# UCirKit30x20-0721.net
KiCad netlist of a schematic drawn in EAGLE
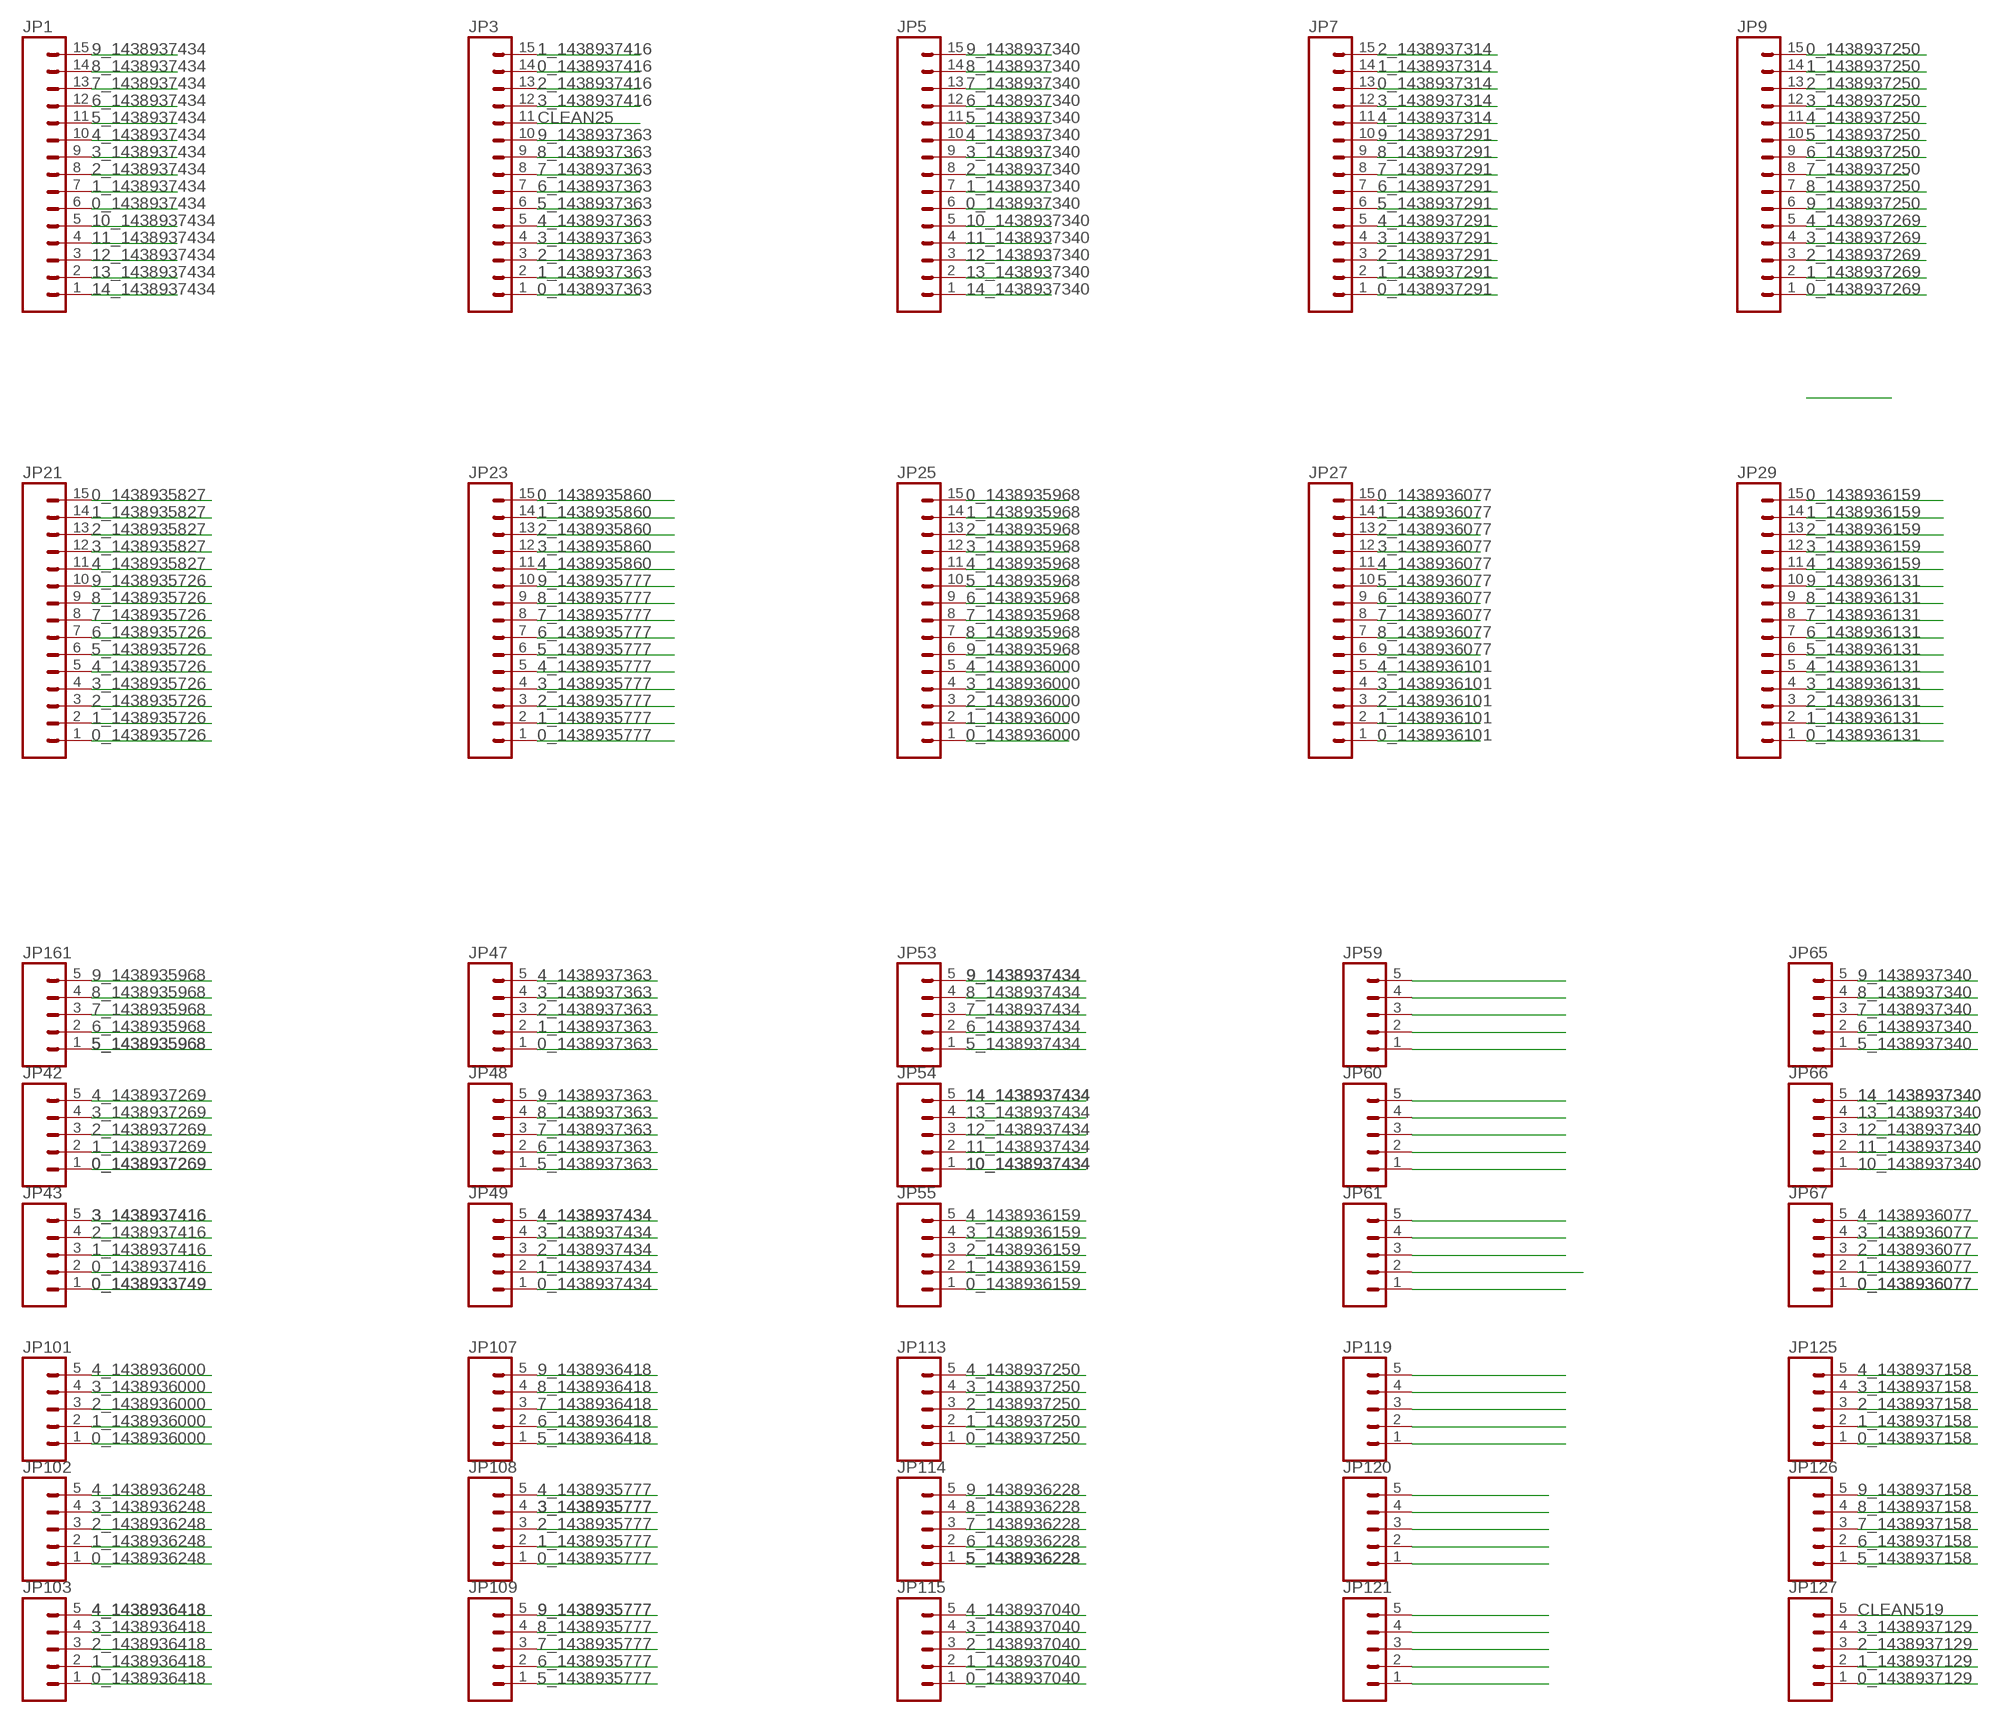
[diagram p0: schematic, sheet 1, part 1 of 2]
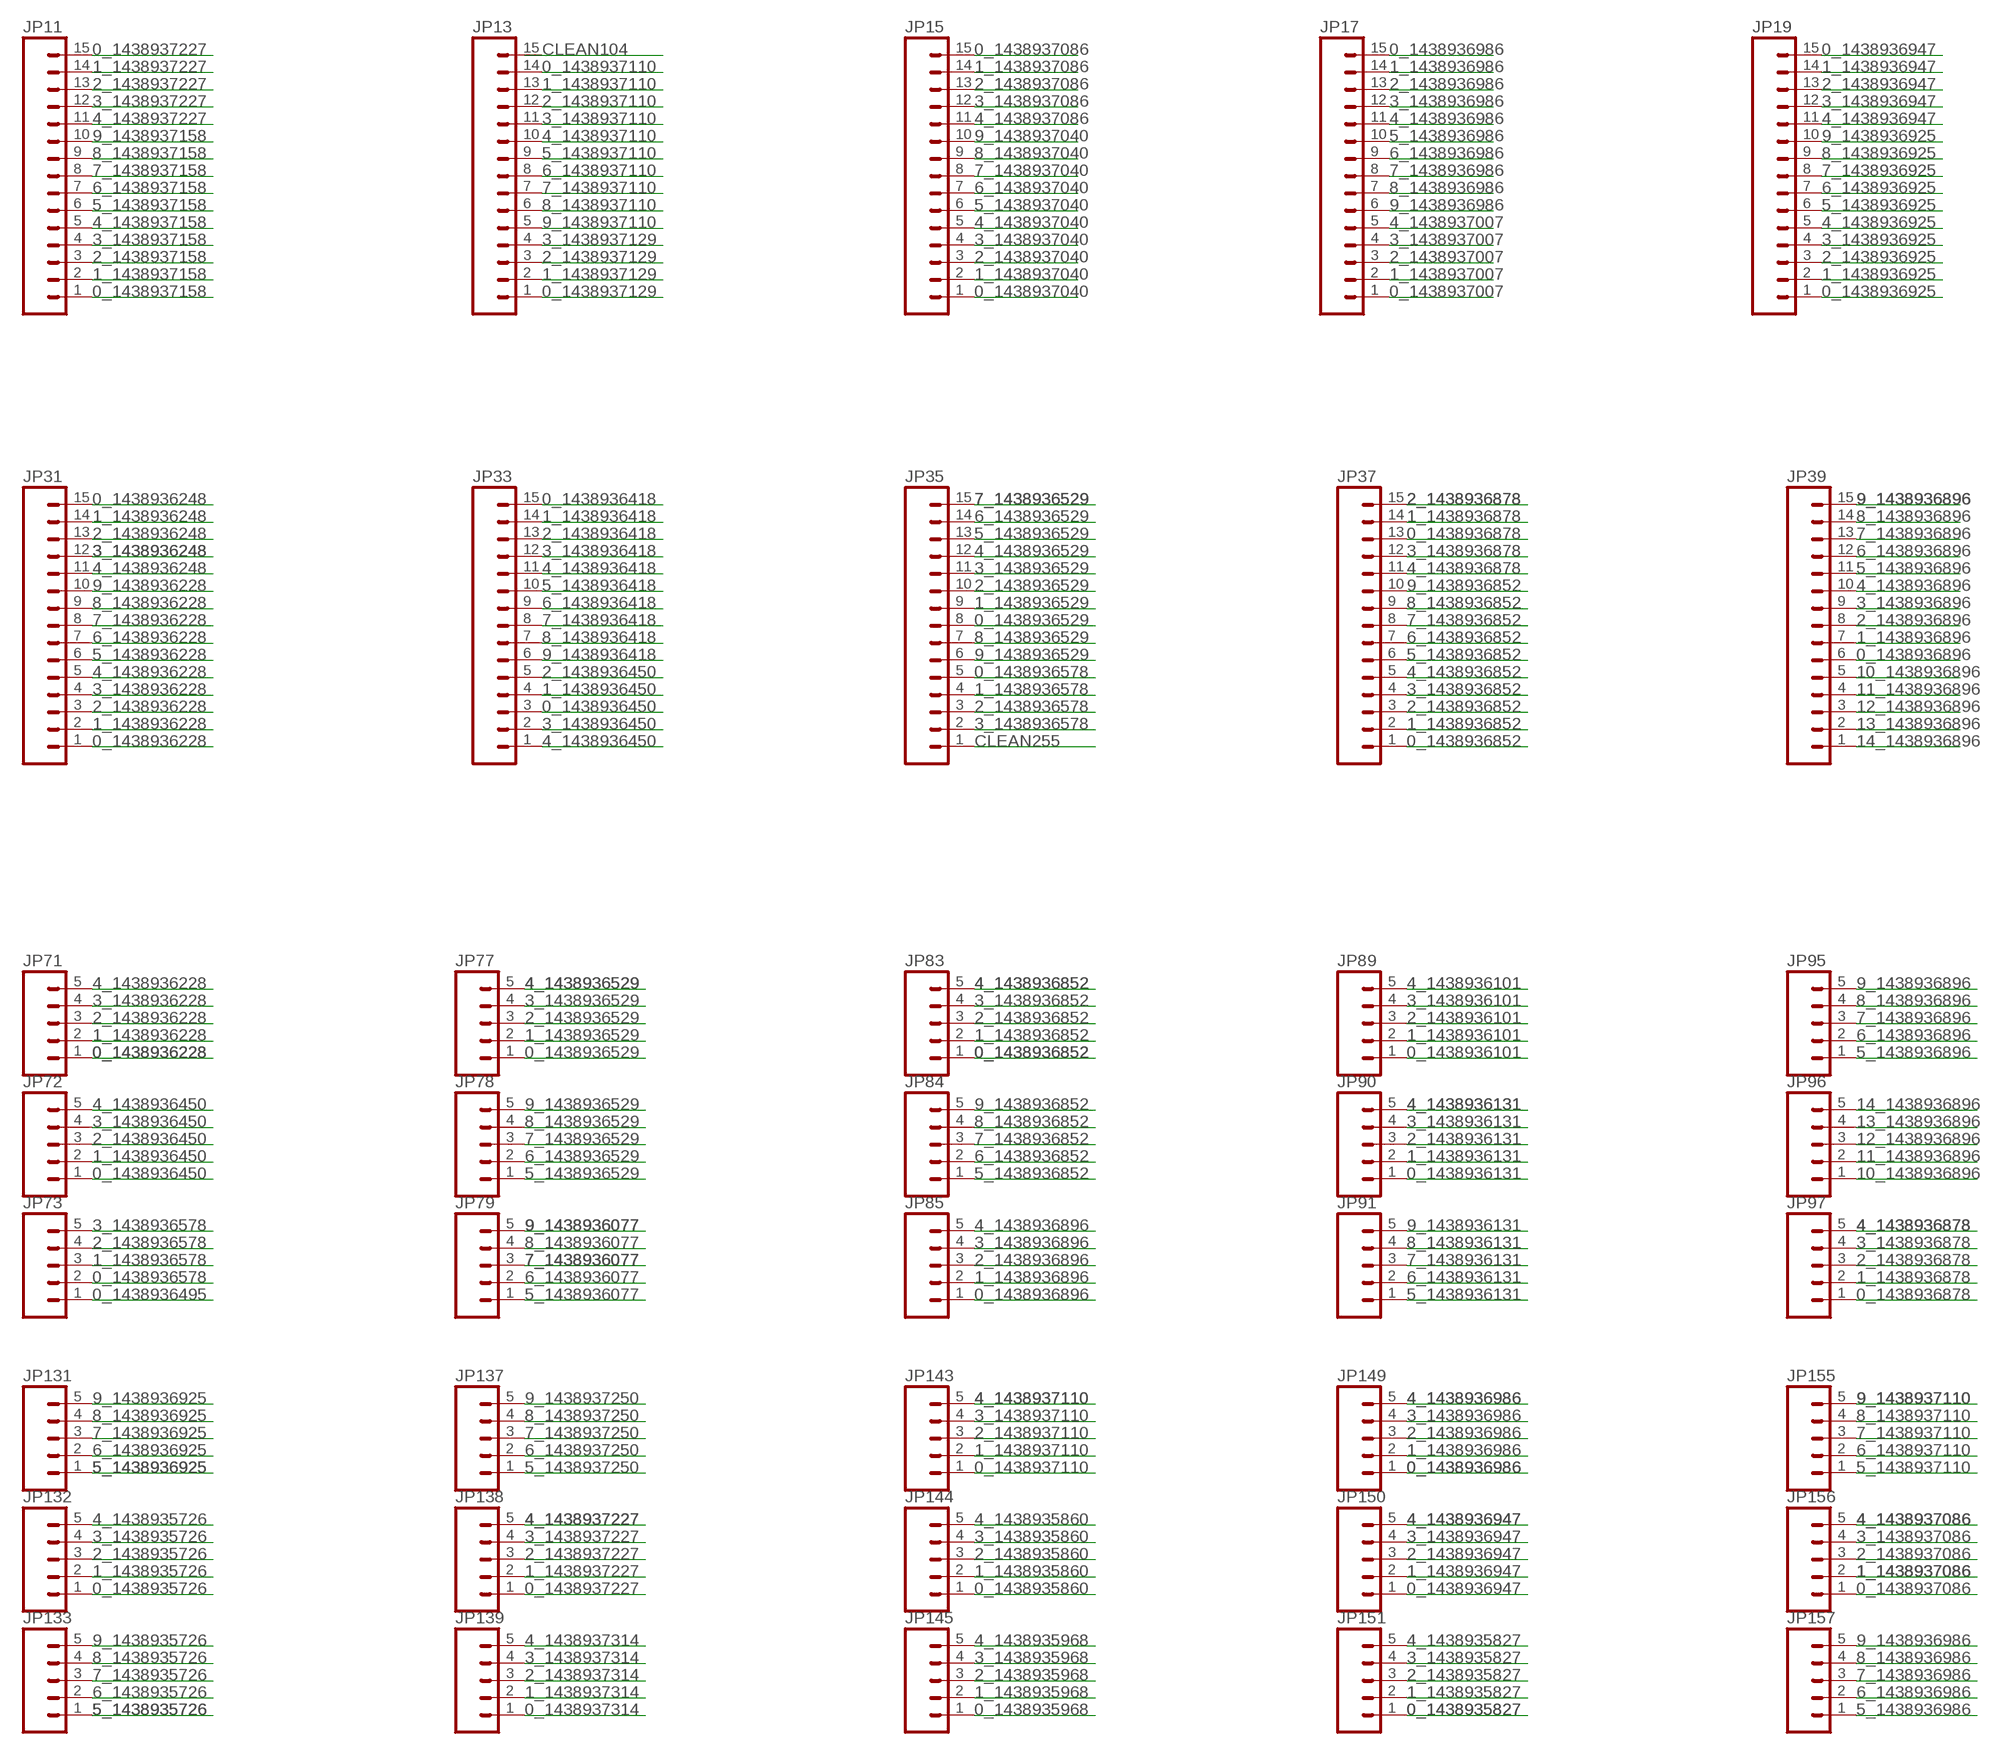
[diagram p1: schematic, sheet 1, part 2 of 2]

(export (version "E")
  (design (tool "Eeschema 10.0.6"))
  (components
    (comp (ref "JP1")
      (value "M15")
      (footprint "eagle-import:1X15")
      (libsource (lib "eagle-import") (part "M15"))
    )
    (comp (ref "JP3")
      (value "M15")
      (footprint "eagle-import:1X15")
      (libsource (lib "eagle-import") (part "M15"))
    )
    (comp (ref "JP5")
      (value "M15")
      (footprint "eagle-import:1X15")
      (libsource (lib "eagle-import") (part "M15"))
    )
    (comp (ref "JP7")
      (value "M15")
      (footprint "eagle-import:1X15")
      (libsource (lib "eagle-import") (part "M15"))
    )
    (comp (ref "JP9")
      (value "M15")
      (footprint "eagle-import:1X15")
      (libsource (lib "eagle-import") (part "M15"))
    )
    (comp (ref "JP11")
      (value "M15")
      (footprint "eagle-import:1X15")
      (libsource (lib "eagle-import") (part "M15"))
    )
    (comp (ref "JP13")
      (value "M15")
      (footprint "eagle-import:1X15")
      (libsource (lib "eagle-import") (part "M15"))
    )
    (comp (ref "JP15")
      (value "M15")
      (footprint "eagle-import:1X15")
      (libsource (lib "eagle-import") (part "M15"))
    )
    (comp (ref "JP17")
      (value "M15")
      (footprint "eagle-import:1X15")
      (libsource (lib "eagle-import") (part "M15"))
    )
    (comp (ref "JP19")
      (value "M15")
      (footprint "eagle-import:1X15")
      (libsource (lib "eagle-import") (part "M15"))
    )
    (comp (ref "JP21")
      (value "M15")
      (footprint "eagle-import:1X15")
      (libsource (lib "eagle-import") (part "M15"))
    )
    (comp (ref "JP23")
      (value "M15")
      (footprint "eagle-import:1X15")
      (libsource (lib "eagle-import") (part "M15"))
    )
    (comp (ref "JP25")
      (value "M15")
      (footprint "eagle-import:1X15")
      (libsource (lib "eagle-import") (part "M15"))
    )
    (comp (ref "JP27")
      (value "M15")
      (footprint "eagle-import:1X15")
      (libsource (lib "eagle-import") (part "M15"))
    )
    (comp (ref "JP29")
      (value "M15")
      (footprint "eagle-import:1X15")
      (libsource (lib "eagle-import") (part "M15"))
    )
    (comp (ref "JP31")
      (value "M15")
      (footprint "eagle-import:1X15")
      (libsource (lib "eagle-import") (part "M15"))
    )
    (comp (ref "JP33")
      (value "M15")
      (footprint "eagle-import:1X15")
      (libsource (lib "eagle-import") (part "M15"))
    )
    (comp (ref "JP35")
      (value "M15")
      (footprint "eagle-import:1X15")
      (libsource (lib "eagle-import") (part "M15"))
    )
    (comp (ref "JP37")
      (value "M15")
      (footprint "eagle-import:1X15")
      (libsource (lib "eagle-import") (part "M15"))
    )
    (comp (ref "JP39")
      (value "M15")
      (footprint "eagle-import:1X15")
      (libsource (lib "eagle-import") (part "M15"))
    )
    (comp (ref "JP42")
      (value "M051.27MM")
      (footprint "eagle-import:1X05-1.27MM")
      (libsource (lib "eagle-import") (part "M051.27MM"))
    )
    (comp (ref "JP43")
      (value "M051.27MM")
      (footprint "eagle-import:1X05-1.27MM")
      (libsource (lib "eagle-import") (part "M051.27MM"))
    )
    (comp (ref "JP47")
      (value "M051.27MM")
      (footprint "eagle-import:1X05-1.27MM")
      (libsource (lib "eagle-import") (part "M051.27MM"))
    )
    (comp (ref "JP48")
      (value "M051.27MM")
      (footprint "eagle-import:1X05-1.27MM")
      (libsource (lib "eagle-import") (part "M051.27MM"))
    )
    (comp (ref "JP49")
      (value "M051.27MM")
      (footprint "eagle-import:1X05-1.27MM")
      (libsource (lib "eagle-import") (part "M051.27MM"))
    )
    (comp (ref "JP53")
      (value "M051.27MM")
      (footprint "eagle-import:1X05-1.27MM")
      (libsource (lib "eagle-import") (part "M051.27MM"))
    )
    (comp (ref "JP54")
      (value "M051.27MM")
      (footprint "eagle-import:1X05-1.27MM")
      (libsource (lib "eagle-import") (part "M051.27MM"))
    )
    (comp (ref "JP55")
      (value "M051.27MM")
      (footprint "eagle-import:1X05-1.27MM")
      (libsource (lib "eagle-import") (part "M051.27MM"))
    )
    (comp (ref "JP59")
      (value "M051.27MM")
      (footprint "eagle-import:1X05-1.27MM")
      (libsource (lib "eagle-import") (part "M051.27MM"))
    )
    (comp (ref "JP60")
      (value "M051.27MM")
      (footprint "eagle-import:1X05-1.27MM")
      (libsource (lib "eagle-import") (part "M051.27MM"))
    )
    (comp (ref "JP61")
      (value "M051.27MM")
      (footprint "eagle-import:1X05-1.27MM")
      (libsource (lib "eagle-import") (part "M051.27MM"))
    )
    (comp (ref "JP65")
      (value "M051.27MM")
      (footprint "eagle-import:1X05-1.27MM")
      (libsource (lib "eagle-import") (part "M051.27MM"))
    )
    (comp (ref "JP66")
      (value "M051.27MM")
      (footprint "eagle-import:1X05-1.27MM")
      (libsource (lib "eagle-import") (part "M051.27MM"))
    )
    (comp (ref "JP67")
      (value "M051.27MM")
      (footprint "eagle-import:1X05-1.27MM")
      (libsource (lib "eagle-import") (part "M051.27MM"))
    )
    (comp (ref "JP71")
      (value "M051.27MM")
      (footprint "eagle-import:1X05-1.27MM")
      (libsource (lib "eagle-import") (part "M051.27MM"))
    )
    (comp (ref "JP72")
      (value "M051.27MM")
      (footprint "eagle-import:1X05-1.27MM")
      (libsource (lib "eagle-import") (part "M051.27MM"))
    )
    (comp (ref "JP73")
      (value "M051.27MM")
      (footprint "eagle-import:1X05-1.27MM")
      (libsource (lib "eagle-import") (part "M051.27MM"))
    )
    (comp (ref "JP77")
      (value "M051.27MM")
      (footprint "eagle-import:1X05-1.27MM")
      (libsource (lib "eagle-import") (part "M051.27MM"))
    )
    (comp (ref "JP78")
      (value "M051.27MM")
      (footprint "eagle-import:1X05-1.27MM")
      (libsource (lib "eagle-import") (part "M051.27MM"))
    )
    (comp (ref "JP79")
      (value "M051.27MM")
      (footprint "eagle-import:1X05-1.27MM")
      (libsource (lib "eagle-import") (part "M051.27MM"))
    )
    (comp (ref "JP83")
      (value "M051.27MM")
      (footprint "eagle-import:1X05-1.27MM")
      (libsource (lib "eagle-import") (part "M051.27MM"))
    )
    (comp (ref "JP84")
      (value "M051.27MM")
      (footprint "eagle-import:1X05-1.27MM")
      (libsource (lib "eagle-import") (part "M051.27MM"))
    )
    (comp (ref "JP85")
      (value "M051.27MM")
      (footprint "eagle-import:1X05-1.27MM")
      (libsource (lib "eagle-import") (part "M051.27MM"))
    )
    (comp (ref "JP89")
      (value "M051.27MM")
      (footprint "eagle-import:1X05-1.27MM")
      (libsource (lib "eagle-import") (part "M051.27MM"))
    )
    (comp (ref "JP90")
      (value "M051.27MM")
      (footprint "eagle-import:1X05-1.27MM")
      (libsource (lib "eagle-import") (part "M051.27MM"))
    )
    (comp (ref "JP91")
      (value "M051.27MM")
      (footprint "eagle-import:1X05-1.27MM")
      (libsource (lib "eagle-import") (part "M051.27MM"))
    )
    (comp (ref "JP95")
      (value "M051.27MM")
      (footprint "eagle-import:1X05-1.27MM")
      (libsource (lib "eagle-import") (part "M051.27MM"))
    )
    (comp (ref "JP96")
      (value "M051.27MM")
      (footprint "eagle-import:1X05-1.27MM")
      (libsource (lib "eagle-import") (part "M051.27MM"))
    )
    (comp (ref "JP97")
      (value "M051.27MM")
      (footprint "eagle-import:1X05-1.27MM")
      (libsource (lib "eagle-import") (part "M051.27MM"))
    )
    (comp (ref "JP101")
      (value "M051.27MM")
      (footprint "eagle-import:1X05-1.27MM")
      (libsource (lib "eagle-import") (part "M051.27MM"))
    )
    (comp (ref "JP102")
      (value "M051.27MM")
      (footprint "eagle-import:1X05-1.27MM")
      (libsource (lib "eagle-import") (part "M051.27MM"))
    )
    (comp (ref "JP103")
      (value "M051.27MM")
      (footprint "eagle-import:1X05-1.27MM")
      (libsource (lib "eagle-import") (part "M051.27MM"))
    )
    (comp (ref "JP107")
      (value "M051.27MM")
      (footprint "eagle-import:1X05-1.27MM")
      (libsource (lib "eagle-import") (part "M051.27MM"))
    )
    (comp (ref "JP108")
      (value "M051.27MM")
      (footprint "eagle-import:1X05-1.27MM")
      (libsource (lib "eagle-import") (part "M051.27MM"))
    )
    (comp (ref "JP109")
      (value "M051.27MM")
      (footprint "eagle-import:1X05-1.27MM")
      (libsource (lib "eagle-import") (part "M051.27MM"))
    )
    (comp (ref "JP113")
      (value "M051.27MM")
      (footprint "eagle-import:1X05-1.27MM")
      (libsource (lib "eagle-import") (part "M051.27MM"))
    )
    (comp (ref "JP114")
      (value "M051.27MM")
      (footprint "eagle-import:1X05-1.27MM")
      (libsource (lib "eagle-import") (part "M051.27MM"))
    )
    (comp (ref "JP115")
      (value "M051.27MM")
      (footprint "eagle-import:1X05-1.27MM")
      (libsource (lib "eagle-import") (part "M051.27MM"))
    )
    (comp (ref "JP119")
      (value "M051.27MM")
      (footprint "eagle-import:1X05-1.27MM")
      (libsource (lib "eagle-import") (part "M051.27MM"))
    )
    (comp (ref "JP120")
      (value "M051.27MM")
      (footprint "eagle-import:1X05-1.27MM")
      (libsource (lib "eagle-import") (part "M051.27MM"))
    )
    (comp (ref "JP121")
      (value "M051.27MM")
      (footprint "eagle-import:1X05-1.27MM")
      (libsource (lib "eagle-import") (part "M051.27MM"))
    )
    (comp (ref "JP125")
      (value "M051.27MM")
      (footprint "eagle-import:1X05-1.27MM")
      (libsource (lib "eagle-import") (part "M051.27MM"))
    )
    (comp (ref "JP126")
      (value "M051.27MM")
      (footprint "eagle-import:1X05-1.27MM")
      (libsource (lib "eagle-import") (part "M051.27MM"))
    )
    (comp (ref "JP127")
      (value "M051.27MM")
      (footprint "eagle-import:1X05-1.27MM")
      (libsource (lib "eagle-import") (part "M051.27MM"))
    )
    (comp (ref "JP131")
      (value "M051.27MM")
      (footprint "eagle-import:1X05-1.27MM")
      (libsource (lib "eagle-import") (part "M051.27MM"))
    )
    (comp (ref "JP132")
      (value "M051.27MM")
      (footprint "eagle-import:1X05-1.27MM")
      (libsource (lib "eagle-import") (part "M051.27MM"))
    )
    (comp (ref "JP133")
      (value "M051.27MM")
      (footprint "eagle-import:1X05-1.27MM")
      (libsource (lib "eagle-import") (part "M051.27MM"))
    )
    (comp (ref "JP137")
      (value "M051.27MM")
      (footprint "eagle-import:1X05-1.27MM")
      (libsource (lib "eagle-import") (part "M051.27MM"))
    )
    (comp (ref "JP138")
      (value "M051.27MM")
      (footprint "eagle-import:1X05-1.27MM")
      (libsource (lib "eagle-import") (part "M051.27MM"))
    )
    (comp (ref "JP139")
      (value "M051.27MM")
      (footprint "eagle-import:1X05-1.27MM")
      (libsource (lib "eagle-import") (part "M051.27MM"))
    )
    (comp (ref "JP143")
      (value "M051.27MM")
      (footprint "eagle-import:1X05-1.27MM")
      (libsource (lib "eagle-import") (part "M051.27MM"))
    )
    (comp (ref "JP144")
      (value "M051.27MM")
      (footprint "eagle-import:1X05-1.27MM")
      (libsource (lib "eagle-import") (part "M051.27MM"))
    )
    (comp (ref "JP145")
      (value "M051.27MM")
      (footprint "eagle-import:1X05-1.27MM")
      (libsource (lib "eagle-import") (part "M051.27MM"))
    )
    (comp (ref "JP149")
      (value "M051.27MM")
      (footprint "eagle-import:1X05-1.27MM")
      (libsource (lib "eagle-import") (part "M051.27MM"))
    )
    (comp (ref "JP150")
      (value "M051.27MM")
      (footprint "eagle-import:1X05-1.27MM")
      (libsource (lib "eagle-import") (part "M051.27MM"))
    )
    (comp (ref "JP151")
      (value "M051.27MM")
      (footprint "eagle-import:1X05-1.27MM")
      (libsource (lib "eagle-import") (part "M051.27MM"))
    )
    (comp (ref "JP155")
      (value "M051.27MM")
      (footprint "eagle-import:1X05-1.27MM")
      (libsource (lib "eagle-import") (part "M051.27MM"))
    )
    (comp (ref "JP156")
      (value "M051.27MM")
      (footprint "eagle-import:1X05-1.27MM")
      (libsource (lib "eagle-import") (part "M051.27MM"))
    )
    (comp (ref "JP157")
      (value "M051.27MM")
      (footprint "eagle-import:1X05-1.27MM")
      (libsource (lib "eagle-import") (part "M051.27MM"))
    )
    (comp (ref "JP161")
      (value "M051.27MM")
      (footprint "eagle-import:1X05-1.27MM")
      (libsource (lib "eagle-import") (part "M051.27MM"))
    )
  )
  (nets
    (net (code "1") (name "/0_1438933749") (class "Default")
      (node (ref "JP43") (pin "1") (pinfunction "1_1") (pintype "passive"))
    )
    (net (code "2") (name "/0_1438935726") (class "Default")
      (node (ref "JP132") (pin "1") (pinfunction "1_1") (pintype "passive"))
      (node (ref "JP21") (pin "1") (pinfunction "1_1") (pintype "passive"))
    )
    (net (code "3") (name "/0_1438935777") (class "Default")
      (node (ref "JP108") (pin "1") (pinfunction "1_1") (pintype "passive"))
      (node (ref "JP23") (pin "1") (pinfunction "1_1") (pintype "passive"))
    )
    (net (code "4") (name "/0_1438935827") (class "Default")
      (node (ref "JP151") (pin "1") (pinfunction "1_1") (pintype "passive"))
      (node (ref "JP21") (pin "15") (pinfunction "15_15") (pintype "passive"))
    )
    (net (code "5") (name "/0_1438935860") (class "Default")
      (node (ref "JP144") (pin "1") (pinfunction "1_1") (pintype "passive"))
      (node (ref "JP23") (pin "15") (pinfunction "15_15") (pintype "passive"))
    )
    (net (code "6") (name "/0_1438935968") (class "Default")
      (node (ref "JP145") (pin "1") (pinfunction "1_1") (pintype "passive"))
      (node (ref "JP25") (pin "15") (pinfunction "15_15") (pintype "passive"))
    )
    (net (code "7") (name "/0_1438936000") (class "Default")
      (node (ref "JP101") (pin "1") (pinfunction "1_1") (pintype "passive"))
      (node (ref "JP25") (pin "1") (pinfunction "1_1") (pintype "passive"))
    )
    (net (code "8") (name "/0_1438936077") (class "Default")
      (node (ref "JP27") (pin "15") (pinfunction "15_15") (pintype "passive"))
      (node (ref "JP67") (pin "1") (pinfunction "1_1") (pintype "passive"))
    )
    (net (code "9") (name "/0_1438936101") (class "Default")
      (node (ref "JP27") (pin "1") (pinfunction "1_1") (pintype "passive"))
      (node (ref "JP89") (pin "1") (pinfunction "1_1") (pintype "passive"))
    )
    (net (code "10") (name "/0_1438936131") (class "Default")
      (node (ref "JP29") (pin "1") (pinfunction "1_1") (pintype "passive"))
      (node (ref "JP90") (pin "1") (pinfunction "1_1") (pintype "passive"))
    )
    (net (code "11") (name "/0_1438936159") (class "Default")
      (node (ref "JP29") (pin "15") (pinfunction "15_15") (pintype "passive"))
      (node (ref "JP55") (pin "1") (pinfunction "1_1") (pintype "passive"))
    )
    (net (code "12") (name "/0_1438936228") (class "Default")
      (node (ref "JP31") (pin "1") (pinfunction "1_1") (pintype "passive"))
      (node (ref "JP71") (pin "1") (pinfunction "1_1") (pintype "passive"))
    )
    (net (code "13") (name "/0_1438936248") (class "Default")
      (node (ref "JP102") (pin "1") (pinfunction "1_1") (pintype "passive"))
      (node (ref "JP31") (pin "15") (pinfunction "15_15") (pintype "passive"))
    )
    (net (code "14") (name "/0_1438936418") (class "Default")
      (node (ref "JP103") (pin "1") (pinfunction "1_1") (pintype "passive"))
      (node (ref "JP33") (pin "15") (pinfunction "15_15") (pintype "passive"))
    )
    (net (code "15") (name "/0_1438936450") (class "Default")
      (node (ref "JP33") (pin "3") (pinfunction "3_3") (pintype "passive"))
      (node (ref "JP72") (pin "1") (pinfunction "1_1") (pintype "passive"))
    )
    (net (code "16") (name "/0_1438936495") (class "Default")
      (node (ref "JP73") (pin "1") (pinfunction "1_1") (pintype "passive"))
    )
    (net (code "17") (name "/0_1438936529") (class "Default")
      (node (ref "JP35") (pin "8") (pinfunction "8_8") (pintype "passive"))
      (node (ref "JP77") (pin "1") (pinfunction "1_1") (pintype "passive"))
    )
    (net (code "18") (name "/0_1438936578") (class "Default")
      (node (ref "JP35") (pin "5") (pinfunction "5_5") (pintype "passive"))
      (node (ref "JP73") (pin "2") (pinfunction "2_2") (pintype "passive"))
    )
    (net (code "19") (name "/0_1438936852") (class "Default")
      (node (ref "JP37") (pin "1") (pinfunction "1_1") (pintype "passive"))
      (node (ref "JP83") (pin "1") (pinfunction "1_1") (pintype "passive"))
    )
    (net (code "20") (name "/0_1438936878") (class "Default")
      (node (ref "JP37") (pin "13") (pinfunction "13_13") (pintype "passive"))
      (node (ref "JP97") (pin "1") (pinfunction "1_1") (pintype "passive"))
    )
    (net (code "21") (name "/0_1438936896") (class "Default")
      (node (ref "JP39") (pin "6") (pinfunction "6_6") (pintype "passive"))
      (node (ref "JP85") (pin "1") (pinfunction "1_1") (pintype "passive"))
    )
    (net (code "22") (name "/0_1438936925") (class "Default")
      (node (ref "JP121") (pin "1") (pinfunction "1_1") (pintype "passive"))
      (node (ref "JP19") (pin "1") (pinfunction "1_1") (pintype "passive"))
    )
    (net (code "23") (name "/0_1438936947") (class "Default")
      (node (ref "JP150") (pin "1") (pinfunction "1_1") (pintype "passive"))
      (node (ref "JP19") (pin "15") (pinfunction "15_15") (pintype "passive"))
    )
    (net (code "24") (name "/0_1438936986") (class "Default")
      (node (ref "JP149") (pin "1") (pinfunction "1_1") (pintype "passive"))
      (node (ref "JP17") (pin "15") (pinfunction "15_15") (pintype "passive"))
    )
    (net (code "25") (name "/0_1438937007") (class "Default")
      (node (ref "JP120") (pin "1") (pinfunction "1_1") (pintype "passive"))
      (node (ref "JP17") (pin "1") (pinfunction "1_1") (pintype "passive"))
    )
    (net (code "26") (name "/0_1438937040") (class "Default")
      (node (ref "JP115") (pin "1") (pinfunction "1_1") (pintype "passive"))
      (node (ref "JP15") (pin "1") (pinfunction "1_1") (pintype "passive"))
    )
    (net (code "27") (name "/0_1438937086") (class "Default")
      (node (ref "JP15") (pin "15") (pinfunction "15_15") (pintype "passive"))
      (node (ref "JP156") (pin "1") (pinfunction "1_1") (pintype "passive"))
    )
    (net (code "28") (name "/0_1438937110") (class "Default")
      (node (ref "JP13") (pin "14") (pinfunction "14_14") (pintype "passive"))
      (node (ref "JP143") (pin "1") (pinfunction "1_1") (pintype "passive"))
    )
    (net (code "29") (name "/0_1438937129") (class "Default")
      (node (ref "JP127") (pin "1") (pinfunction "1_1") (pintype "passive"))
      (node (ref "JP13") (pin "1") (pinfunction "1_1") (pintype "passive"))
    )
    (net (code "30") (name "/0_1438937158") (class "Default")
      (node (ref "JP11") (pin "1") (pinfunction "1_1") (pintype "passive"))
      (node (ref "JP125") (pin "1") (pinfunction "1_1") (pintype "passive"))
    )
    (net (code "31") (name "/0_1438937227") (class "Default")
      (node (ref "JP11") (pin "15") (pinfunction "15_15") (pintype "passive"))
      (node (ref "JP138") (pin "1") (pinfunction "1_1") (pintype "passive"))
    )
    (net (code "32") (name "/0_1438937250") (class "Default")
      (node (ref "JP113") (pin "1") (pinfunction "1_1") (pintype "passive"))
      (node (ref "JP9") (pin "15") (pinfunction "15_15") (pintype "passive"))
    )
    (net (code "33") (name "/0_1438937269") (class "Default")
      (node (ref "JP42") (pin "1") (pinfunction "1_1") (pintype "passive"))
      (node (ref "JP9") (pin "1") (pinfunction "1_1") (pintype "passive"))
    )
    (net (code "34") (name "/0_1438937291") (class "Default")
      (node (ref "JP59") (pin "1") (pinfunction "1_1") (pintype "passive"))
      (node (ref "JP7") (pin "1") (pinfunction "1_1") (pintype "passive"))
    )
    (net (code "35") (name "/0_1438937314") (class "Default")
      (node (ref "JP139") (pin "1") (pinfunction "1_1") (pintype "passive"))
      (node (ref "JP7") (pin "13") (pinfunction "13_13") (pintype "passive"))
    )
    (net (code "36") (name "/0_1438937340") (class "Default")
      (node (ref "JP5") (pin "6") (pinfunction "6_6") (pintype "passive"))
      (node (ref "JP61") (pin "1") (pinfunction "1_1") (pintype "passive"))
    )
    (net (code "37") (name "/0_1438937363") (class "Default")
      (node (ref "JP3") (pin "1") (pinfunction "1_1") (pintype "passive"))
      (node (ref "JP47") (pin "1") (pinfunction "1_1") (pintype "passive"))
    )
    (net (code "38") (name "/0_1438937416") (class "Default")
      (node (ref "JP3") (pin "14") (pinfunction "14_14") (pintype "passive"))
      (node (ref "JP43") (pin "2") (pinfunction "2_2") (pintype "passive"))
    )
    (net (code "39") (name "/0_1438937434") (class "Default")
      (node (ref "JP1") (pin "6") (pinfunction "6_6") (pintype "passive"))
      (node (ref "JP49") (pin "1") (pinfunction "1_1") (pintype "passive"))
    )
    (net (code "40") (name "/1_1438935726") (class "Default")
      (node (ref "JP132") (pin "2") (pinfunction "2_2") (pintype "passive"))
      (node (ref "JP21") (pin "2") (pinfunction "2_2") (pintype "passive"))
    )
    (net (code "41") (name "/1_1438935777") (class "Default")
      (node (ref "JP108") (pin "2") (pinfunction "2_2") (pintype "passive"))
      (node (ref "JP23") (pin "2") (pinfunction "2_2") (pintype "passive"))
    )
    (net (code "42") (name "/1_1438935827") (class "Default")
      (node (ref "JP151") (pin "2") (pinfunction "2_2") (pintype "passive"))
      (node (ref "JP21") (pin "14") (pinfunction "14_14") (pintype "passive"))
    )
    (net (code "43") (name "/1_1438935860") (class "Default")
      (node (ref "JP144") (pin "2") (pinfunction "2_2") (pintype "passive"))
      (node (ref "JP23") (pin "14") (pinfunction "14_14") (pintype "passive"))
    )
    (net (code "44") (name "/1_1438935968") (class "Default")
      (node (ref "JP145") (pin "2") (pinfunction "2_2") (pintype "passive"))
      (node (ref "JP25") (pin "14") (pinfunction "14_14") (pintype "passive"))
    )
    (net (code "45") (name "/1_1438936000") (class "Default")
      (node (ref "JP101") (pin "2") (pinfunction "2_2") (pintype "passive"))
      (node (ref "JP25") (pin "2") (pinfunction "2_2") (pintype "passive"))
    )
    (net (code "46") (name "/1_1438936077") (class "Default")
      (node (ref "JP27") (pin "14") (pinfunction "14_14") (pintype "passive"))
      (node (ref "JP67") (pin "2") (pinfunction "2_2") (pintype "passive"))
    )
    (net (code "47") (name "/1_1438936101") (class "Default")
      (node (ref "JP27") (pin "2") (pinfunction "2_2") (pintype "passive"))
      (node (ref "JP89") (pin "2") (pinfunction "2_2") (pintype "passive"))
    )
    (net (code "48") (name "/1_1438936131") (class "Default")
      (node (ref "JP29") (pin "2") (pinfunction "2_2") (pintype "passive"))
      (node (ref "JP90") (pin "2") (pinfunction "2_2") (pintype "passive"))
    )
    (net (code "49") (name "/1_1438936159") (class "Default")
      (node (ref "JP29") (pin "14") (pinfunction "14_14") (pintype "passive"))
      (node (ref "JP55") (pin "2") (pinfunction "2_2") (pintype "passive"))
    )
    (net (code "50") (name "/1_1438936228") (class "Default")
      (node (ref "JP31") (pin "2") (pinfunction "2_2") (pintype "passive"))
      (node (ref "JP71") (pin "2") (pinfunction "2_2") (pintype "passive"))
    )
    (net (code "51") (name "/1_1438936248") (class "Default")
      (node (ref "JP102") (pin "2") (pinfunction "2_2") (pintype "passive"))
      (node (ref "JP31") (pin "14") (pinfunction "14_14") (pintype "passive"))
    )
    (net (code "52") (name "/1_1438936418") (class "Default")
      (node (ref "JP103") (pin "2") (pinfunction "2_2") (pintype "passive"))
      (node (ref "JP33") (pin "14") (pinfunction "14_14") (pintype "passive"))
    )
    (net (code "53") (name "/1_1438936450") (class "Default")
      (node (ref "JP33") (pin "4") (pinfunction "4_4") (pintype "passive"))
      (node (ref "JP72") (pin "2") (pinfunction "2_2") (pintype "passive"))
    )
    (net (code "54") (name "/1_1438936529") (class "Default")
      (node (ref "JP35") (pin "9") (pinfunction "9_9") (pintype "passive"))
      (node (ref "JP77") (pin "2") (pinfunction "2_2") (pintype "passive"))
    )
    (net (code "55") (name "/1_1438936578") (class "Default")
      (node (ref "JP35") (pin "4") (pinfunction "4_4") (pintype "passive"))
      (node (ref "JP73") (pin "3") (pinfunction "3_3") (pintype "passive"))
    )
    (net (code "56") (name "/1_1438936852") (class "Default")
      (node (ref "JP37") (pin "2") (pinfunction "2_2") (pintype "passive"))
      (node (ref "JP83") (pin "2") (pinfunction "2_2") (pintype "passive"))
    )
    (net (code "57") (name "/1_1438936878") (class "Default")
      (node (ref "JP37") (pin "14") (pinfunction "14_14") (pintype "passive"))
      (node (ref "JP97") (pin "2") (pinfunction "2_2") (pintype "passive"))
    )
    (net (code "58") (name "/1_1438936896") (class "Default")
      (node (ref "JP39") (pin "7") (pinfunction "7_7") (pintype "passive"))
      (node (ref "JP85") (pin "2") (pinfunction "2_2") (pintype "passive"))
    )
    (net (code "59") (name "/1_1438936925") (class "Default")
      (node (ref "JP121") (pin "2") (pinfunction "2_2") (pintype "passive"))
      (node (ref "JP19") (pin "2") (pinfunction "2_2") (pintype "passive"))
    )
    (net (code "60") (name "/1_1438936947") (class "Default")
      (node (ref "JP150") (pin "2") (pinfunction "2_2") (pintype "passive"))
      (node (ref "JP19") (pin "14") (pinfunction "14_14") (pintype "passive"))
    )
    (net (code "61") (name "/1_1438936986") (class "Default")
      (node (ref "JP149") (pin "2") (pinfunction "2_2") (pintype "passive"))
      (node (ref "JP17") (pin "14") (pinfunction "14_14") (pintype "passive"))
    )
    (net (code "62") (name "/1_1438937007") (class "Default")
      (node (ref "JP120") (pin "2") (pinfunction "2_2") (pintype "passive"))
      (node (ref "JP17") (pin "2") (pinfunction "2_2") (pintype "passive"))
    )
    (net (code "63") (name "/1_1438937040") (class "Default")
      (node (ref "JP115") (pin "2") (pinfunction "2_2") (pintype "passive"))
      (node (ref "JP15") (pin "2") (pinfunction "2_2") (pintype "passive"))
    )
    (net (code "64") (name "/1_1438937086") (class "Default")
      (node (ref "JP15") (pin "14") (pinfunction "14_14") (pintype "passive"))
      (node (ref "JP156") (pin "2") (pinfunction "2_2") (pintype "passive"))
    )
    (net (code "65") (name "/1_1438937110") (class "Default")
      (node (ref "JP13") (pin "13") (pinfunction "13_13") (pintype "passive"))
      (node (ref "JP143") (pin "2") (pinfunction "2_2") (pintype "passive"))
    )
    (net (code "66") (name "/1_1438937129") (class "Default")
      (node (ref "JP127") (pin "2") (pinfunction "2_2") (pintype "passive"))
      (node (ref "JP13") (pin "2") (pinfunction "2_2") (pintype "passive"))
    )
    (net (code "67") (name "/1_1438937158") (class "Default")
      (node (ref "JP11") (pin "2") (pinfunction "2_2") (pintype "passive"))
      (node (ref "JP125") (pin "2") (pinfunction "2_2") (pintype "passive"))
    )
    (net (code "68") (name "/1_1438937227") (class "Default")
      (node (ref "JP11") (pin "14") (pinfunction "14_14") (pintype "passive"))
      (node (ref "JP138") (pin "2") (pinfunction "2_2") (pintype "passive"))
    )
    (net (code "69") (name "/1_1438937250") (class "Default")
      (node (ref "JP113") (pin "2") (pinfunction "2_2") (pintype "passive"))
      (node (ref "JP9") (pin "14") (pinfunction "14_14") (pintype "passive"))
    )
    (net (code "70") (name "/1_1438937269") (class "Default")
      (node (ref "JP42") (pin "2") (pinfunction "2_2") (pintype "passive"))
      (node (ref "JP9") (pin "2") (pinfunction "2_2") (pintype "passive"))
    )
    (net (code "71") (name "/1_1438937291") (class "Default")
      (node (ref "JP59") (pin "2") (pinfunction "2_2") (pintype "passive"))
      (node (ref "JP7") (pin "2") (pinfunction "2_2") (pintype "passive"))
    )
    (net (code "72") (name "/1_1438937314") (class "Default")
      (node (ref "JP139") (pin "2") (pinfunction "2_2") (pintype "passive"))
      (node (ref "JP7") (pin "14") (pinfunction "14_14") (pintype "passive"))
    )
    (net (code "73") (name "/1_1438937340") (class "Default")
      (node (ref "JP5") (pin "7") (pinfunction "7_7") (pintype "passive"))
      (node (ref "JP61") (pin "2") (pinfunction "2_2") (pintype "passive"))
    )
    (net (code "74") (name "/1_1438937363") (class "Default")
      (node (ref "JP3") (pin "2") (pinfunction "2_2") (pintype "passive"))
      (node (ref "JP47") (pin "2") (pinfunction "2_2") (pintype "passive"))
    )
    (net (code "75") (name "/1_1438937416") (class "Default")
      (node (ref "JP3") (pin "15") (pinfunction "15_15") (pintype "passive"))
      (node (ref "JP43") (pin "3") (pinfunction "3_3") (pintype "passive"))
    )
    (net (code "76") (name "/1_1438937434") (class "Default")
      (node (ref "JP1") (pin "7") (pinfunction "7_7") (pintype "passive"))
      (node (ref "JP49") (pin "2") (pinfunction "2_2") (pintype "passive"))
    )
    (net (code "77") (name "/2_1438935726") (class "Default")
      (node (ref "JP132") (pin "3") (pinfunction "3_3") (pintype "passive"))
      (node (ref "JP21") (pin "3") (pinfunction "3_3") (pintype "passive"))
    )
    (net (code "78") (name "/2_1438935777") (class "Default")
      (node (ref "JP108") (pin "3") (pinfunction "3_3") (pintype "passive"))
      (node (ref "JP23") (pin "3") (pinfunction "3_3") (pintype "passive"))
    )
    (net (code "79") (name "/2_1438935827") (class "Default")
      (node (ref "JP151") (pin "3") (pinfunction "3_3") (pintype "passive"))
      (node (ref "JP21") (pin "13") (pinfunction "13_13") (pintype "passive"))
    )
    (net (code "80") (name "/2_1438935860") (class "Default")
      (node (ref "JP144") (pin "3") (pinfunction "3_3") (pintype "passive"))
      (node (ref "JP23") (pin "13") (pinfunction "13_13") (pintype "passive"))
    )
    (net (code "81") (name "/2_1438935968") (class "Default")
      (node (ref "JP145") (pin "3") (pinfunction "3_3") (pintype "passive"))
      (node (ref "JP25") (pin "13") (pinfunction "13_13") (pintype "passive"))
    )
    (net (code "82") (name "/2_1438936000") (class "Default")
      (node (ref "JP101") (pin "3") (pinfunction "3_3") (pintype "passive"))
      (node (ref "JP25") (pin "3") (pinfunction "3_3") (pintype "passive"))
    )
    (net (code "83") (name "/2_1438936077") (class "Default")
      (node (ref "JP27") (pin "13") (pinfunction "13_13") (pintype "passive"))
      (node (ref "JP67") (pin "3") (pinfunction "3_3") (pintype "passive"))
    )
    (net (code "84") (name "/2_1438936101") (class "Default")
      (node (ref "JP27") (pin "3") (pinfunction "3_3") (pintype "passive"))
      (node (ref "JP89") (pin "3") (pinfunction "3_3") (pintype "passive"))
    )
    (net (code "85") (name "/2_1438936131") (class "Default")
      (node (ref "JP29") (pin "3") (pinfunction "3_3") (pintype "passive"))
      (node (ref "JP90") (pin "3") (pinfunction "3_3") (pintype "passive"))
    )
    (net (code "86") (name "/2_1438936159") (class "Default")
      (node (ref "JP29") (pin "13") (pinfunction "13_13") (pintype "passive"))
      (node (ref "JP55") (pin "3") (pinfunction "3_3") (pintype "passive"))
    )
    (net (code "87") (name "/2_1438936228") (class "Default")
      (node (ref "JP31") (pin "3") (pinfunction "3_3") (pintype "passive"))
      (node (ref "JP71") (pin "3") (pinfunction "3_3") (pintype "passive"))
    )
    (net (code "88") (name "/2_1438936248") (class "Default")
      (node (ref "JP102") (pin "3") (pinfunction "3_3") (pintype "passive"))
      (node (ref "JP31") (pin "13") (pinfunction "13_13") (pintype "passive"))
    )
    (net (code "89") (name "/2_1438936418") (class "Default")
      (node (ref "JP103") (pin "3") (pinfunction "3_3") (pintype "passive"))
      (node (ref "JP33") (pin "13") (pinfunction "13_13") (pintype "passive"))
    )
    (net (code "90") (name "/2_1438936450") (class "Default")
      (node (ref "JP33") (pin "5") (pinfunction "5_5") (pintype "passive"))
      (node (ref "JP72") (pin "3") (pinfunction "3_3") (pintype "passive"))
    )
    (net (code "91") (name "/2_1438936529") (class "Default")
      (node (ref "JP35") (pin "10") (pinfunction "10_10") (pintype "passive"))
      (node (ref "JP77") (pin "3") (pinfunction "3_3") (pintype "passive"))
    )
    (net (code "92") (name "/2_1438936578") (class "Default")
      (node (ref "JP35") (pin "3") (pinfunction "3_3") (pintype "passive"))
      (node (ref "JP73") (pin "4") (pinfunction "4_4") (pintype "passive"))
    )
    (net (code "93") (name "/2_1438936852") (class "Default")
      (node (ref "JP37") (pin "3") (pinfunction "3_3") (pintype "passive"))
      (node (ref "JP83") (pin "3") (pinfunction "3_3") (pintype "passive"))
    )
    (net (code "94") (name "/2_1438936878") (class "Default")
      (node (ref "JP37") (pin "15") (pinfunction "15_15") (pintype "passive"))
      (node (ref "JP97") (pin "3") (pinfunction "3_3") (pintype "passive"))
    )
    (net (code "95") (name "/2_1438936896") (class "Default")
      (node (ref "JP39") (pin "8") (pinfunction "8_8") (pintype "passive"))
      (node (ref "JP85") (pin "3") (pinfunction "3_3") (pintype "passive"))
    )
    (net (code "96") (name "/2_1438936925") (class "Default")
      (node (ref "JP121") (pin "3") (pinfunction "3_3") (pintype "passive"))
      (node (ref "JP19") (pin "3") (pinfunction "3_3") (pintype "passive"))
    )
    (net (code "97") (name "/2_1438936947") (class "Default")
      (node (ref "JP150") (pin "3") (pinfunction "3_3") (pintype "passive"))
      (node (ref "JP19") (pin "13") (pinfunction "13_13") (pintype "passive"))
    )
    (net (code "98") (name "/2_1438936986") (class "Default")
      (node (ref "JP149") (pin "3") (pinfunction "3_3") (pintype "passive"))
      (node (ref "JP17") (pin "13") (pinfunction "13_13") (pintype "passive"))
    )
    (net (code "99") (name "/2_1438937007") (class "Default")
      (node (ref "JP120") (pin "3") (pinfunction "3_3") (pintype "passive"))
      (node (ref "JP17") (pin "3") (pinfunction "3_3") (pintype "passive"))
    )
    (net (code "100") (name "/2_1438937040") (class "Default")
      (node (ref "JP115") (pin "3") (pinfunction "3_3") (pintype "passive"))
      (node (ref "JP15") (pin "3") (pinfunction "3_3") (pintype "passive"))
    )
    (net (code "101") (name "/2_1438937086") (class "Default")
      (node (ref "JP15") (pin "13") (pinfunction "13_13") (pintype "passive"))
      (node (ref "JP156") (pin "3") (pinfunction "3_3") (pintype "passive"))
    )
    (net (code "102") (name "/2_1438937110") (class "Default")
      (node (ref "JP13") (pin "12") (pinfunction "12_12") (pintype "passive"))
      (node (ref "JP143") (pin "3") (pinfunction "3_3") (pintype "passive"))
    )
    (net (code "103") (name "/2_1438937129") (class "Default")
      (node (ref "JP127") (pin "3") (pinfunction "3_3") (pintype "passive"))
      (node (ref "JP13") (pin "3") (pinfunction "3_3") (pintype "passive"))
    )
    (net (code "104") (name "/2_1438937158") (class "Default")
      (node (ref "JP11") (pin "3") (pinfunction "3_3") (pintype "passive"))
      (node (ref "JP125") (pin "3") (pinfunction "3_3") (pintype "passive"))
    )
    (net (code "105") (name "/2_1438937227") (class "Default")
      (node (ref "JP11") (pin "13") (pinfunction "13_13") (pintype "passive"))
      (node (ref "JP138") (pin "3") (pinfunction "3_3") (pintype "passive"))
    )
    (net (code "106") (name "/2_1438937250") (class "Default")
      (node (ref "JP113") (pin "3") (pinfunction "3_3") (pintype "passive"))
      (node (ref "JP9") (pin "13") (pinfunction "13_13") (pintype "passive"))
    )
    (net (code "107") (name "/2_1438937269") (class "Default")
      (node (ref "JP42") (pin "3") (pinfunction "3_3") (pintype "passive"))
      (node (ref "JP9") (pin "3") (pinfunction "3_3") (pintype "passive"))
    )
    (net (code "108") (name "/2_1438937291") (class "Default")
      (node (ref "JP59") (pin "3") (pinfunction "3_3") (pintype "passive"))
      (node (ref "JP7") (pin "3") (pinfunction "3_3") (pintype "passive"))
    )
    (net (code "109") (name "/2_1438937314") (class "Default")
      (node (ref "JP139") (pin "3") (pinfunction "3_3") (pintype "passive"))
      (node (ref "JP7") (pin "15") (pinfunction "15_15") (pintype "passive"))
    )
    (net (code "110") (name "/2_1438937340") (class "Default")
      (node (ref "JP5") (pin "8") (pinfunction "8_8") (pintype "passive"))
      (node (ref "JP61") (pin "3") (pinfunction "3_3") (pintype "passive"))
    )
    (net (code "111") (name "/2_1438937363") (class "Default")
      (node (ref "JP3") (pin "3") (pinfunction "3_3") (pintype "passive"))
      (node (ref "JP47") (pin "3") (pinfunction "3_3") (pintype "passive"))
    )
    (net (code "112") (name "/2_1438937416") (class "Default")
      (node (ref "JP3") (pin "13") (pinfunction "13_13") (pintype "passive"))
      (node (ref "JP43") (pin "4") (pinfunction "4_4") (pintype "passive"))
    )
    (net (code "113") (name "/2_1438937434") (class "Default")
      (node (ref "JP1") (pin "8") (pinfunction "8_8") (pintype "passive"))
      (node (ref "JP49") (pin "3") (pinfunction "3_3") (pintype "passive"))
    )
    (net (code "114") (name "/3_1438935726") (class "Default")
      (node (ref "JP132") (pin "4") (pinfunction "4_4") (pintype "passive"))
      (node (ref "JP21") (pin "4") (pinfunction "4_4") (pintype "passive"))
    )
    (net (code "115") (name "/3_1438935777") (class "Default")
      (node (ref "JP108") (pin "4") (pinfunction "4_4") (pintype "passive"))
      (node (ref "JP23") (pin "4") (pinfunction "4_4") (pintype "passive"))
    )
    (net (code "116") (name "/3_1438935827") (class "Default")
      (node (ref "JP151") (pin "4") (pinfunction "4_4") (pintype "passive"))
      (node (ref "JP21") (pin "12") (pinfunction "12_12") (pintype "passive"))
    )
    (net (code "117") (name "/3_1438935860") (class "Default")
      (node (ref "JP144") (pin "4") (pinfunction "4_4") (pintype "passive"))
      (node (ref "JP23") (pin "12") (pinfunction "12_12") (pintype "passive"))
    )
    (net (code "118") (name "/3_1438935968") (class "Default")
      (node (ref "JP145") (pin "4") (pinfunction "4_4") (pintype "passive"))
      (node (ref "JP25") (pin "12") (pinfunction "12_12") (pintype "passive"))
    )
    (net (code "119") (name "/3_1438936000") (class "Default")
      (node (ref "JP101") (pin "4") (pinfunction "4_4") (pintype "passive"))
      (node (ref "JP25") (pin "4") (pinfunction "4_4") (pintype "passive"))
    )
    (net (code "120") (name "/3_1438936077") (class "Default")
      (node (ref "JP27") (pin "12") (pinfunction "12_12") (pintype "passive"))
      (node (ref "JP67") (pin "4") (pinfunction "4_4") (pintype "passive"))
    )
    (net (code "121") (name "/3_1438936101") (class "Default")
      (node (ref "JP27") (pin "4") (pinfunction "4_4") (pintype "passive"))
      (node (ref "JP89") (pin "4") (pinfunction "4_4") (pintype "passive"))
    )
    (net (code "122") (name "/3_1438936131") (class "Default")
      (node (ref "JP29") (pin "4") (pinfunction "4_4") (pintype "passive"))
      (node (ref "JP90") (pin "4") (pinfunction "4_4") (pintype "passive"))
    )
    (net (code "123") (name "/3_1438936159") (class "Default")
      (node (ref "JP29") (pin "12") (pinfunction "12_12") (pintype "passive"))
      (node (ref "JP55") (pin "4") (pinfunction "4_4") (pintype "passive"))
    )
    (net (code "124") (name "/3_1438936228") (class "Default")
      (node (ref "JP31") (pin "4") (pinfunction "4_4") (pintype "passive"))
      (node (ref "JP71") (pin "4") (pinfunction "4_4") (pintype "passive"))
    )
    (net (code "125") (name "/3_1438936248") (class "Default")
      (node (ref "JP102") (pin "4") (pinfunction "4_4") (pintype "passive"))
      (node (ref "JP31") (pin "12") (pinfunction "12_12") (pintype "passive"))
    )
    (net (code "126") (name "/3_1438936418") (class "Default")
      (node (ref "JP103") (pin "4") (pinfunction "4_4") (pintype "passive"))
      (node (ref "JP33") (pin "12") (pinfunction "12_12") (pintype "passive"))
    )
    (net (code "127") (name "/3_1438936450") (class "Default")
      (node (ref "JP33") (pin "2") (pinfunction "2_2") (pintype "passive"))
      (node (ref "JP72") (pin "4") (pinfunction "4_4") (pintype "passive"))
    )
    (net (code "128") (name "/3_1438936529") (class "Default")
      (node (ref "JP35") (pin "11") (pinfunction "11_11") (pintype "passive"))
      (node (ref "JP77") (pin "4") (pinfunction "4_4") (pintype "passive"))
    )
    (net (code "129") (name "/3_1438936578") (class "Default")
      (node (ref "JP35") (pin "2") (pinfunction "2_2") (pintype "passive"))
      (node (ref "JP73") (pin "5") (pinfunction "5_5") (pintype "passive"))
    )
    (net (code "130") (name "/3_1438936852") (class "Default")
      (node (ref "JP37") (pin "4") (pinfunction "4_4") (pintype "passive"))
      (node (ref "JP83") (pin "4") (pinfunction "4_4") (pintype "passive"))
    )
    (net (code "131") (name "/3_1438936878") (class "Default")
      (node (ref "JP37") (pin "12") (pinfunction "12_12") (pintype "passive"))
      (node (ref "JP97") (pin "4") (pinfunction "4_4") (pintype "passive"))
    )
    (net (code "132") (name "/3_1438936896") (class "Default")
      (node (ref "JP39") (pin "9") (pinfunction "9_9") (pintype "passive"))
      (node (ref "JP85") (pin "4") (pinfunction "4_4") (pintype "passive"))
    )
    (net (code "133") (name "/3_1438936925") (class "Default")
      (node (ref "JP121") (pin "4") (pinfunction "4_4") (pintype "passive"))
      (node (ref "JP19") (pin "4") (pinfunction "4_4") (pintype "passive"))
    )
    (net (code "134") (name "/3_1438936947") (class "Default")
      (node (ref "JP150") (pin "4") (pinfunction "4_4") (pintype "passive"))
      (node (ref "JP19") (pin "12") (pinfunction "12_12") (pintype "passive"))
    )
    (net (code "135") (name "/3_1438936986") (class "Default")
      (node (ref "JP149") (pin "4") (pinfunction "4_4") (pintype "passive"))
      (node (ref "JP17") (pin "12") (pinfunction "12_12") (pintype "passive"))
    )
    (net (code "136") (name "/3_1438937007") (class "Default")
      (node (ref "JP120") (pin "4") (pinfunction "4_4") (pintype "passive"))
      (node (ref "JP17") (pin "4") (pinfunction "4_4") (pintype "passive"))
    )
    (net (code "137") (name "/3_1438937040") (class "Default")
      (node (ref "JP115") (pin "4") (pinfunction "4_4") (pintype "passive"))
      (node (ref "JP15") (pin "4") (pinfunction "4_4") (pintype "passive"))
    )
    (net (code "138") (name "/3_1438937086") (class "Default")
      (node (ref "JP15") (pin "12") (pinfunction "12_12") (pintype "passive"))
      (node (ref "JP156") (pin "4") (pinfunction "4_4") (pintype "passive"))
    )
    (net (code "139") (name "/3_1438937110") (class "Default")
      (node (ref "JP13") (pin "11") (pinfunction "11_11") (pintype "passive"))
      (node (ref "JP143") (pin "4") (pinfunction "4_4") (pintype "passive"))
    )
    (net (code "140") (name "/3_1438937129") (class "Default")
      (node (ref "JP127") (pin "4") (pinfunction "4_4") (pintype "passive"))
      (node (ref "JP13") (pin "4") (pinfunction "4_4") (pintype "passive"))
    )
    (net (code "141") (name "/3_1438937158") (class "Default")
      (node (ref "JP11") (pin "4") (pinfunction "4_4") (pintype "passive"))
      (node (ref "JP125") (pin "4") (pinfunction "4_4") (pintype "passive"))
    )
    (net (code "142") (name "/3_1438937227") (class "Default")
      (node (ref "JP11") (pin "12") (pinfunction "12_12") (pintype "passive"))
      (node (ref "JP138") (pin "4") (pinfunction "4_4") (pintype "passive"))
    )
    (net (code "143") (name "/3_1438937250") (class "Default")
      (node (ref "JP113") (pin "4") (pinfunction "4_4") (pintype "passive"))
      (node (ref "JP9") (pin "12") (pinfunction "12_12") (pintype "passive"))
    )
    (net (code "144") (name "/3_1438937269") (class "Default")
      (node (ref "JP42") (pin "4") (pinfunction "4_4") (pintype "passive"))
      (node (ref "JP9") (pin "4") (pinfunction "4_4") (pintype "passive"))
    )
    (net (code "145") (name "/3_1438937291") (class "Default")
      (node (ref "JP59") (pin "4") (pinfunction "4_4") (pintype "passive"))
      (node (ref "JP7") (pin "4") (pinfunction "4_4") (pintype "passive"))
    )
    (net (code "146") (name "/3_1438937314") (class "Default")
      (node (ref "JP139") (pin "4") (pinfunction "4_4") (pintype "passive"))
      (node (ref "JP7") (pin "12") (pinfunction "12_12") (pintype "passive"))
    )
    (net (code "147") (name "/3_1438937340") (class "Default")
      (node (ref "JP5") (pin "9") (pinfunction "9_9") (pintype "passive"))
      (node (ref "JP61") (pin "4") (pinfunction "4_4") (pintype "passive"))
    )
    (net (code "148") (name "/3_1438937363") (class "Default")
      (node (ref "JP3") (pin "4") (pinfunction "4_4") (pintype "passive"))
      (node (ref "JP47") (pin "4") (pinfunction "4_4") (pintype "passive"))
    )
    (net (code "149") (name "/3_1438937416") (class "Default")
      (node (ref "JP3") (pin "12") (pinfunction "12_12") (pintype "passive"))
      (node (ref "JP43") (pin "5") (pinfunction "5_5") (pintype "passive"))
    )
    (net (code "150") (name "/3_1438937434") (class "Default")
      (node (ref "JP1") (pin "9") (pinfunction "9_9") (pintype "passive"))
      (node (ref "JP49") (pin "4") (pinfunction "4_4") (pintype "passive"))
    )
    (net (code "151") (name "/4_1438935726") (class "Default")
      (node (ref "JP132") (pin "5") (pinfunction "5_5") (pintype "passive"))
      (node (ref "JP21") (pin "5") (pinfunction "5_5") (pintype "passive"))
    )
    (net (code "152") (name "/4_1438935777") (class "Default")
      (node (ref "JP108") (pin "5") (pinfunction "5_5") (pintype "passive"))
      (node (ref "JP23") (pin "5") (pinfunction "5_5") (pintype "passive"))
    )
    (net (code "153") (name "/4_1438935827") (class "Default")
      (node (ref "JP151") (pin "5") (pinfunction "5_5") (pintype "passive"))
      (node (ref "JP21") (pin "11") (pinfunction "11_11") (pintype "passive"))
    )
    (net (code "154") (name "/4_1438935860") (class "Default")
      (node (ref "JP144") (pin "5") (pinfunction "5_5") (pintype "passive"))
      (node (ref "JP23") (pin "11") (pinfunction "11_11") (pintype "passive"))
    )
    (net (code "155") (name "/4_1438935968") (class "Default")
      (node (ref "JP145") (pin "5") (pinfunction "5_5") (pintype "passive"))
      (node (ref "JP25") (pin "11") (pinfunction "11_11") (pintype "passive"))
    )
    (net (code "156") (name "/4_1438936000") (class "Default")
      (node (ref "JP101") (pin "5") (pinfunction "5_5") (pintype "passive"))
      (node (ref "JP25") (pin "5") (pinfunction "5_5") (pintype "passive"))
    )
    (net (code "157") (name "/4_1438936077") (class "Default")
      (node (ref "JP27") (pin "11") (pinfunction "11_11") (pintype "passive"))
      (node (ref "JP67") (pin "5") (pinfunction "5_5") (pintype "passive"))
    )
    (net (code "158") (name "/4_1438936101") (class "Default")
      (node (ref "JP27") (pin "5") (pinfunction "5_5") (pintype "passive"))
      (node (ref "JP89") (pin "5") (pinfunction "5_5") (pintype "passive"))
    )
    (net (code "159") (name "/4_1438936131") (class "Default")
      (node (ref "JP29") (pin "5") (pinfunction "5_5") (pintype "passive"))
      (node (ref "JP90") (pin "5") (pinfunction "5_5") (pintype "passive"))
    )
    (net (code "160") (name "/4_1438936159") (class "Default")
      (node (ref "JP29") (pin "11") (pinfunction "11_11") (pintype "passive"))
      (node (ref "JP55") (pin "5") (pinfunction "5_5") (pintype "passive"))
    )
    (net (code "161") (name "/4_1438936228") (class "Default")
      (node (ref "JP31") (pin "5") (pinfunction "5_5") (pintype "passive"))
      (node (ref "JP71") (pin "5") (pinfunction "5_5") (pintype "passive"))
    )
    (net (code "162") (name "/4_1438936248") (class "Default")
      (node (ref "JP102") (pin "5") (pinfunction "5_5") (pintype "passive"))
      (node (ref "JP31") (pin "11") (pinfunction "11_11") (pintype "passive"))
    )
    (net (code "163") (name "/4_1438936418") (class "Default")
      (node (ref "JP103") (pin "5") (pinfunction "5_5") (pintype "passive"))
      (node (ref "JP33") (pin "11") (pinfunction "11_11") (pintype "passive"))
    )
    (net (code "164") (name "/4_1438936450") (class "Default")
      (node (ref "JP33") (pin "1") (pinfunction "1_1") (pintype "passive"))
      (node (ref "JP72") (pin "5") (pinfunction "5_5") (pintype "passive"))
    )
    (net (code "165") (name "/4_1438936529") (class "Default")
      (node (ref "JP35") (pin "12") (pinfunction "12_12") (pintype "passive"))
      (node (ref "JP77") (pin "5") (pinfunction "5_5") (pintype "passive"))
    )
    (net (code "166") (name "/4_1438936852") (class "Default")
      (node (ref "JP37") (pin "5") (pinfunction "5_5") (pintype "passive"))
      (node (ref "JP83") (pin "5") (pinfunction "5_5") (pintype "passive"))
    )
    (net (code "167") (name "/4_1438936878") (class "Default")
      (node (ref "JP37") (pin "11") (pinfunction "11_11") (pintype "passive"))
      (node (ref "JP97") (pin "5") (pinfunction "5_5") (pintype "passive"))
    )
    (net (code "168") (name "/4_1438936896") (class "Default")
      (node (ref "JP39") (pin "10") (pinfunction "10_10") (pintype "passive"))
      (node (ref "JP85") (pin "5") (pinfunction "5_5") (pintype "passive"))
    )
    (net (code "169") (name "/4_1438936925") (class "Default")
      (node (ref "JP121") (pin "5") (pinfunction "5_5") (pintype "passive"))
      (node (ref "JP19") (pin "5") (pinfunction "5_5") (pintype "passive"))
    )
    (net (code "170") (name "/4_1438936947") (class "Default")
      (node (ref "JP150") (pin "5") (pinfunction "5_5") (pintype "passive"))
      (node (ref "JP19") (pin "11") (pinfunction "11_11") (pintype "passive"))
    )
    (net (code "171") (name "/4_1438936986") (class "Default")
      (node (ref "JP149") (pin "5") (pinfunction "5_5") (pintype "passive"))
      (node (ref "JP17") (pin "11") (pinfunction "11_11") (pintype "passive"))
    )
    (net (code "172") (name "/4_1438937007") (class "Default")
      (node (ref "JP120") (pin "5") (pinfunction "5_5") (pintype "passive"))
      (node (ref "JP17") (pin "5") (pinfunction "5_5") (pintype "passive"))
    )
    (net (code "173") (name "/4_1438937040") (class "Default")
      (node (ref "JP115") (pin "5") (pinfunction "5_5") (pintype "passive"))
      (node (ref "JP15") (pin "5") (pinfunction "5_5") (pintype "passive"))
    )
    (net (code "174") (name "/4_1438937086") (class "Default")
      (node (ref "JP15") (pin "11") (pinfunction "11_11") (pintype "passive"))
      (node (ref "JP156") (pin "5") (pinfunction "5_5") (pintype "passive"))
    )
    (net (code "175") (name "/4_1438937110") (class "Default")
      (node (ref "JP13") (pin "10") (pinfunction "10_10") (pintype "passive"))
      (node (ref "JP143") (pin "5") (pinfunction "5_5") (pintype "passive"))
    )
    (net (code "176") (name "/4_1438937158") (class "Default")
      (node (ref "JP11") (pin "5") (pinfunction "5_5") (pintype "passive"))
      (node (ref "JP125") (pin "5") (pinfunction "5_5") (pintype "passive"))
    )
    (net (code "177") (name "/4_1438937227") (class "Default")
      (node (ref "JP11") (pin "11") (pinfunction "11_11") (pintype "passive"))
      (node (ref "JP138") (pin "5") (pinfunction "5_5") (pintype "passive"))
    )
    (net (code "178") (name "/4_1438937250") (class "Default")
      (node (ref "JP113") (pin "5") (pinfunction "5_5") (pintype "passive"))
      (node (ref "JP9") (pin "11") (pinfunction "11_11") (pintype "passive"))
    )
    (net (code "179") (name "/4_1438937269") (class "Default")
      (node (ref "JP42") (pin "5") (pinfunction "5_5") (pintype "passive"))
      (node (ref "JP9") (pin "5") (pinfunction "5_5") (pintype "passive"))
    )
    (net (code "180") (name "/4_1438937291") (class "Default")
      (node (ref "JP59") (pin "5") (pinfunction "5_5") (pintype "passive"))
      (node (ref "JP7") (pin "5") (pinfunction "5_5") (pintype "passive"))
    )
    (net (code "181") (name "/4_1438937314") (class "Default")
      (node (ref "JP139") (pin "5") (pinfunction "5_5") (pintype "passive"))
      (node (ref "JP7") (pin "11") (pinfunction "11_11") (pintype "passive"))
    )
    (net (code "182") (name "/4_1438937340") (class "Default")
      (node (ref "JP5") (pin "10") (pinfunction "10_10") (pintype "passive"))
      (node (ref "JP61") (pin "5") (pinfunction "5_5") (pintype "passive"))
    )
    (net (code "183") (name "/4_1438937363") (class "Default")
      (node (ref "JP3") (pin "5") (pinfunction "5_5") (pintype "passive"))
      (node (ref "JP47") (pin "5") (pinfunction "5_5") (pintype "passive"))
    )
    (net (code "184") (name "/4_1438937434") (class "Default")
      (node (ref "JP1") (pin "10") (pinfunction "10_10") (pintype "passive"))
      (node (ref "JP49") (pin "5") (pinfunction "5_5") (pintype "passive"))
    )
    (net (code "185") (name "/5_1438935726") (class "Default")
      (node (ref "JP133") (pin "1") (pinfunction "1_1") (pintype "passive"))
      (node (ref "JP21") (pin "6") (pinfunction "6_6") (pintype "passive"))
    )
    (net (code "186") (name "/5_1438935777") (class "Default")
      (node (ref "JP109") (pin "1") (pinfunction "1_1") (pintype "passive"))
      (node (ref "JP23") (pin "6") (pinfunction "6_6") (pintype "passive"))
    )
    (net (code "187") (name "/5_1438935968") (class "Default")
      (node (ref "JP161") (pin "1") (pinfunction "1_1") (pintype "passive"))
      (node (ref "JP25") (pin "10") (pinfunction "10_10") (pintype "passive"))
    )
    (net (code "188") (name "/5_1438936077") (class "Default")
      (node (ref "JP27") (pin "10") (pinfunction "10_10") (pintype "passive"))
      (node (ref "JP79") (pin "1") (pinfunction "1_1") (pintype "passive"))
    )
    (net (code "189") (name "/5_1438936131") (class "Default")
      (node (ref "JP29") (pin "6") (pinfunction "6_6") (pintype "passive"))
      (node (ref "JP91") (pin "1") (pinfunction "1_1") (pintype "passive"))
    )
    (net (code "190") (name "/5_1438936228") (class "Default")
      (node (ref "JP114") (pin "1") (pinfunction "1_1") (pintype "passive"))
      (node (ref "JP31") (pin "6") (pinfunction "6_6") (pintype "passive"))
    )
    (net (code "191") (name "/5_1438936418") (class "Default")
      (node (ref "JP107") (pin "1") (pinfunction "1_1") (pintype "passive"))
      (node (ref "JP33") (pin "10") (pinfunction "10_10") (pintype "passive"))
    )
    (net (code "192") (name "/5_1438936529") (class "Default")
      (node (ref "JP35") (pin "13") (pinfunction "13_13") (pintype "passive"))
      (node (ref "JP78") (pin "1") (pinfunction "1_1") (pintype "passive"))
    )
    (net (code "193") (name "/5_1438936852") (class "Default")
      (node (ref "JP37") (pin "6") (pinfunction "6_6") (pintype "passive"))
      (node (ref "JP84") (pin "1") (pinfunction "1_1") (pintype "passive"))
    )
    (net (code "194") (name "/5_1438936896") (class "Default")
      (node (ref "JP39") (pin "11") (pinfunction "11_11") (pintype "passive"))
      (node (ref "JP95") (pin "1") (pinfunction "1_1") (pintype "passive"))
    )
    (net (code "195") (name "/5_1438936925") (class "Default")
      (node (ref "JP131") (pin "1") (pinfunction "1_1") (pintype "passive"))
      (node (ref "JP19") (pin "6") (pinfunction "6_6") (pintype "passive"))
    )
    (net (code "196") (name "/5_1438936986") (class "Default")
      (node (ref "JP157") (pin "1") (pinfunction "1_1") (pintype "passive"))
      (node (ref "JP17") (pin "10") (pinfunction "10_10") (pintype "passive"))
    )
    (net (code "197") (name "/5_1438937040") (class "Default")
      (node (ref "JP119") (pin "1") (pinfunction "1_1") (pintype "passive"))
      (node (ref "JP15") (pin "6") (pinfunction "6_6") (pintype "passive"))
    )
    (net (code "198") (name "/5_1438937110") (class "Default")
      (node (ref "JP13") (pin "9") (pinfunction "9_9") (pintype "passive"))
      (node (ref "JP155") (pin "1") (pinfunction "1_1") (pintype "passive"))
    )
    (net (code "199") (name "/5_1438937158") (class "Default")
      (node (ref "JP11") (pin "6") (pinfunction "6_6") (pintype "passive"))
      (node (ref "JP126") (pin "1") (pinfunction "1_1") (pintype "passive"))
    )
    (net (code "200") (name "/5_1438937250") (class "Default")
      (node (ref "JP137") (pin "1") (pinfunction "1_1") (pintype "passive"))
      (node (ref "JP9") (pin "10") (pinfunction "10_10") (pintype "passive"))
    )
    (net (code "201") (name "/5_1438937291") (class "Default")
      (node (ref "JP60") (pin "1") (pinfunction "1_1") (pintype "passive"))
      (node (ref "JP7") (pin "6") (pinfunction "6_6") (pintype "passive"))
    )
    (net (code "202") (name "/5_1438937340") (class "Default")
      (node (ref "JP5") (pin "11") (pinfunction "11_11") (pintype "passive"))
      (node (ref "JP65") (pin "1") (pinfunction "1_1") (pintype "passive"))
    )
    (net (code "203") (name "/5_1438937363") (class "Default")
      (node (ref "JP3") (pin "6") (pinfunction "6_6") (pintype "passive"))
      (node (ref "JP48") (pin "1") (pinfunction "1_1") (pintype "passive"))
    )
    (net (code "204") (name "/5_1438937434") (class "Default")
      (node (ref "JP1") (pin "11") (pinfunction "11_11") (pintype "passive"))
      (node (ref "JP53") (pin "1") (pinfunction "1_1") (pintype "passive"))
    )
    (net (code "205") (name "/6_1438935726") (class "Default")
      (node (ref "JP133") (pin "2") (pinfunction "2_2") (pintype "passive"))
      (node (ref "JP21") (pin "7") (pinfunction "7_7") (pintype "passive"))
    )
    (net (code "206") (name "/6_1438935777") (class "Default")
      (node (ref "JP109") (pin "2") (pinfunction "2_2") (pintype "passive"))
      (node (ref "JP23") (pin "7") (pinfunction "7_7") (pintype "passive"))
    )
    (net (code "207") (name "/6_1438935968") (class "Default")
      (node (ref "JP161") (pin "2") (pinfunction "2_2") (pintype "passive"))
      (node (ref "JP25") (pin "9") (pinfunction "9_9") (pintype "passive"))
    )
    (net (code "208") (name "/6_1438936077") (class "Default")
      (node (ref "JP27") (pin "9") (pinfunction "9_9") (pintype "passive"))
      (node (ref "JP79") (pin "2") (pinfunction "2_2") (pintype "passive"))
    )
    (net (code "209") (name "/6_1438936131") (class "Default")
      (node (ref "JP29") (pin "7") (pinfunction "7_7") (pintype "passive"))
      (node (ref "JP91") (pin "2") (pinfunction "2_2") (pintype "passive"))
    )
    (net (code "210") (name "/6_1438936228") (class "Default")
      (node (ref "JP114") (pin "2") (pinfunction "2_2") (pintype "passive"))
      (node (ref "JP31") (pin "7") (pinfunction "7_7") (pintype "passive"))
    )
    (net (code "211") (name "/6_1438936418") (class "Default")
      (node (ref "JP107") (pin "2") (pinfunction "2_2") (pintype "passive"))
      (node (ref "JP33") (pin "9") (pinfunction "9_9") (pintype "passive"))
    )
    (net (code "212") (name "/6_1438936529") (class "Default")
      (node (ref "JP35") (pin "14") (pinfunction "14_14") (pintype "passive"))
      (node (ref "JP78") (pin "2") (pinfunction "2_2") (pintype "passive"))
    )
    (net (code "213") (name "/6_1438936852") (class "Default")
      (node (ref "JP37") (pin "7") (pinfunction "7_7") (pintype "passive"))
      (node (ref "JP84") (pin "2") (pinfunction "2_2") (pintype "passive"))
    )
    (net (code "214") (name "/6_1438936896") (class "Default")
      (node (ref "JP39") (pin "12") (pinfunction "12_12") (pintype "passive"))
      (node (ref "JP95") (pin "2") (pinfunction "2_2") (pintype "passive"))
    )
    (net (code "215") (name "/6_1438936925") (class "Default")
      (node (ref "JP131") (pin "2") (pinfunction "2_2") (pintype "passive"))
      (node (ref "JP19") (pin "7") (pinfunction "7_7") (pintype "passive"))
    )
    (net (code "216") (name "/6_1438936986") (class "Default")
      (node (ref "JP157") (pin "2") (pinfunction "2_2") (pintype "passive"))
      (node (ref "JP17") (pin "9") (pinfunction "9_9") (pintype "passive"))
    )
    (net (code "217") (name "/6_1438937040") (class "Default")
      (node (ref "JP119") (pin "2") (pinfunction "2_2") (pintype "passive"))
      (node (ref "JP15") (pin "7") (pinfunction "7_7") (pintype "passive"))
    )
    (net (code "218") (name "/6_1438937110") (class "Default")
      (node (ref "JP13") (pin "8") (pinfunction "8_8") (pintype "passive"))
      (node (ref "JP155") (pin "2") (pinfunction "2_2") (pintype "passive"))
    )
    (net (code "219") (name "/6_1438937158") (class "Default")
      (node (ref "JP11") (pin "7") (pinfunction "7_7") (pintype "passive"))
      (node (ref "JP126") (pin "2") (pinfunction "2_2") (pintype "passive"))
    )
    (net (code "220") (name "/6_1438937250") (class "Default")
      (node (ref "JP137") (pin "2") (pinfunction "2_2") (pintype "passive"))
      (node (ref "JP9") (pin "9") (pinfunction "9_9") (pintype "passive"))
    )
    (net (code "221") (name "/6_1438937291") (class "Default")
      (node (ref "JP60") (pin "2") (pinfunction "2_2") (pintype "passive"))
      (node (ref "JP7") (pin "7") (pinfunction "7_7") (pintype "passive"))
    )
    (net (code "222") (name "/6_1438937340") (class "Default")
      (node (ref "JP5") (pin "12") (pinfunction "12_12") (pintype "passive"))
      (node (ref "JP65") (pin "2") (pinfunction "2_2") (pintype "passive"))
    )
    (net (code "223") (name "/6_1438937363") (class "Default")
      (node (ref "JP3") (pin "7") (pinfunction "7_7") (pintype "passive"))
      (node (ref "JP48") (pin "2") (pinfunction "2_2") (pintype "passive"))
    )
    (net (code "224") (name "/6_1438937434") (class "Default")
      (node (ref "JP1") (pin "12") (pinfunction "12_12") (pintype "passive"))
      (node (ref "JP53") (pin "2") (pinfunction "2_2") (pintype "passive"))
    )
    (net (code "225") (name "/7_1438935726") (class "Default")
      (node (ref "JP133") (pin "3") (pinfunction "3_3") (pintype "passive"))
      (node (ref "JP21") (pin "8") (pinfunction "8_8") (pintype "passive"))
    )
    (net (code "226") (name "/7_1438935777") (class "Default")
      (node (ref "JP109") (pin "3") (pinfunction "3_3") (pintype "passive"))
      (node (ref "JP23") (pin "8") (pinfunction "8_8") (pintype "passive"))
    )
    (net (code "227") (name "/7_1438935968") (class "Default")
      (node (ref "JP161") (pin "3") (pinfunction "3_3") (pintype "passive"))
      (node (ref "JP25") (pin "8") (pinfunction "8_8") (pintype "passive"))
    )
    (net (code "228") (name "/7_1438936077") (class "Default")
      (node (ref "JP27") (pin "8") (pinfunction "8_8") (pintype "passive"))
      (node (ref "JP79") (pin "3") (pinfunction "3_3") (pintype "passive"))
    )
    (net (code "229") (name "/7_1438936131") (class "Default")
      (node (ref "JP29") (pin "8") (pinfunction "8_8") (pintype "passive"))
      (node (ref "JP91") (pin "3") (pinfunction "3_3") (pintype "passive"))
    )
    (net (code "230") (name "/7_1438936228") (class "Default")
      (node (ref "JP114") (pin "3") (pinfunction "3_3") (pintype "passive"))
      (node (ref "JP31") (pin "8") (pinfunction "8_8") (pintype "passive"))
    )
    (net (code "231") (name "/7_1438936418") (class "Default")
      (node (ref "JP107") (pin "3") (pinfunction "3_3") (pintype "passive"))
      (node (ref "JP33") (pin "8") (pinfunction "8_8") (pintype "passive"))
    )
    (net (code "232") (name "/7_1438936529") (class "Default")
      (node (ref "JP35") (pin "15") (pinfunction "15_15") (pintype "passive"))
      (node (ref "JP78") (pin "3") (pinfunction "3_3") (pintype "passive"))
    )
    (net (code "233") (name "/7_1438936852") (class "Default")
      (node (ref "JP37") (pin "8") (pinfunction "8_8") (pintype "passive"))
      (node (ref "JP84") (pin "3") (pinfunction "3_3") (pintype "passive"))
    )
    (net (code "234") (name "/7_1438936896") (class "Default")
      (node (ref "JP39") (pin "13") (pinfunction "13_13") (pintype "passive"))
      (node (ref "JP95") (pin "3") (pinfunction "3_3") (pintype "passive"))
    )
    (net (code "235") (name "/7_1438936925") (class "Default")
      (node (ref "JP131") (pin "3") (pinfunction "3_3") (pintype "passive"))
      (node (ref "JP19") (pin "8") (pinfunction "8_8") (pintype "passive"))
    )
    (net (code "236") (name "/7_1438936986") (class "Default")
      (node (ref "JP157") (pin "3") (pinfunction "3_3") (pintype "passive"))
      (node (ref "JP17") (pin "8") (pinfunction "8_8") (pintype "passive"))
    )
    (net (code "237") (name "/7_1438937040") (class "Default")
      (node (ref "JP119") (pin "3") (pinfunction "3_3") (pintype "passive"))
      (node (ref "JP15") (pin "8") (pinfunction "8_8") (pintype "passive"))
    )
    (net (code "238") (name "/7_1438937110") (class "Default")
      (node (ref "JP13") (pin "7") (pinfunction "7_7") (pintype "passive"))
      (node (ref "JP155") (pin "3") (pinfunction "3_3") (pintype "passive"))
    )
    (net (code "239") (name "/7_1438937158") (class "Default")
      (node (ref "JP11") (pin "8") (pinfunction "8_8") (pintype "passive"))
      (node (ref "JP126") (pin "3") (pinfunction "3_3") (pintype "passive"))
    )
    (net (code "240") (name "/7_1438937250") (class "Default")
      (node (ref "JP137") (pin "3") (pinfunction "3_3") (pintype "passive"))
      (node (ref "JP9") (pin "8") (pinfunction "8_8") (pintype "passive"))
    )
    (net (code "241") (name "/7_1438937291") (class "Default")
      (node (ref "JP60") (pin "3") (pinfunction "3_3") (pintype "passive"))
      (node (ref "JP7") (pin "8") (pinfunction "8_8") (pintype "passive"))
    )
    (net (code "242") (name "/7_1438937340") (class "Default")
      (node (ref "JP5") (pin "13") (pinfunction "13_13") (pintype "passive"))
      (node (ref "JP65") (pin "3") (pinfunction "3_3") (pintype "passive"))
    )
    (net (code "243") (name "/7_1438937363") (class "Default")
      (node (ref "JP3") (pin "8") (pinfunction "8_8") (pintype "passive"))
      (node (ref "JP48") (pin "3") (pinfunction "3_3") (pintype "passive"))
    )
    (net (code "244") (name "/7_1438937434") (class "Default")
      (node (ref "JP1") (pin "13") (pinfunction "13_13") (pintype "passive"))
      (node (ref "JP53") (pin "3") (pinfunction "3_3") (pintype "passive"))
    )
    (net (code "245") (name "/8_1438935726") (class "Default")
      (node (ref "JP133") (pin "4") (pinfunction "4_4") (pintype "passive"))
      (node (ref "JP21") (pin "9") (pinfunction "9_9") (pintype "passive"))
    )
    (net (code "246") (name "/8_1438935777") (class "Default")
      (node (ref "JP109") (pin "4") (pinfunction "4_4") (pintype "passive"))
      (node (ref "JP23") (pin "9") (pinfunction "9_9") (pintype "passive"))
    )
    (net (code "247") (name "/8_1438935968") (class "Default")
      (node (ref "JP161") (pin "4") (pinfunction "4_4") (pintype "passive"))
      (node (ref "JP25") (pin "7") (pinfunction "7_7") (pintype "passive"))
    )
    (net (code "248") (name "/8_1438936077") (class "Default")
      (node (ref "JP27") (pin "7") (pinfunction "7_7") (pintype "passive"))
      (node (ref "JP79") (pin "4") (pinfunction "4_4") (pintype "passive"))
    )
    (net (code "249") (name "/8_1438936131") (class "Default")
      (node (ref "JP29") (pin "9") (pinfunction "9_9") (pintype "passive"))
      (node (ref "JP91") (pin "4") (pinfunction "4_4") (pintype "passive"))
    )
    (net (code "250") (name "/8_1438936228") (class "Default")
      (node (ref "JP114") (pin "4") (pinfunction "4_4") (pintype "passive"))
      (node (ref "JP31") (pin "9") (pinfunction "9_9") (pintype "passive"))
    )
    (net (code "251") (name "/8_1438936418") (class "Default")
      (node (ref "JP107") (pin "4") (pinfunction "4_4") (pintype "passive"))
      (node (ref "JP33") (pin "7") (pinfunction "7_7") (pintype "passive"))
    )
    (net (code "252") (name "/8_1438936529") (class "Default")
      (node (ref "JP35") (pin "7") (pinfunction "7_7") (pintype "passive"))
      (node (ref "JP78") (pin "4") (pinfunction "4_4") (pintype "passive"))
    )
    (net (code "253") (name "/8_1438936852") (class "Default")
      (node (ref "JP37") (pin "9") (pinfunction "9_9") (pintype "passive"))
      (node (ref "JP84") (pin "4") (pinfunction "4_4") (pintype "passive"))
    )
    (net (code "254") (name "/8_1438936896") (class "Default")
      (node (ref "JP39") (pin "14") (pinfunction "14_14") (pintype "passive"))
      (node (ref "JP95") (pin "4") (pinfunction "4_4") (pintype "passive"))
    )
    (net (code "255") (name "/8_1438936925") (class "Default")
      (node (ref "JP131") (pin "4") (pinfunction "4_4") (pintype "passive"))
      (node (ref "JP19") (pin "9") (pinfunction "9_9") (pintype "passive"))
    )
    (net (code "256") (name "/8_1438936986") (class "Default")
      (node (ref "JP157") (pin "4") (pinfunction "4_4") (pintype "passive"))
      (node (ref "JP17") (pin "7") (pinfunction "7_7") (pintype "passive"))
    )
    (net (code "257") (name "/8_1438937040") (class "Default")
      (node (ref "JP119") (pin "4") (pinfunction "4_4") (pintype "passive"))
      (node (ref "JP15") (pin "9") (pinfunction "9_9") (pintype "passive"))
    )
    (net (code "258") (name "/8_1438937110") (class "Default")
      (node (ref "JP13") (pin "6") (pinfunction "6_6") (pintype "passive"))
      (node (ref "JP155") (pin "4") (pinfunction "4_4") (pintype "passive"))
    )
    (net (code "259") (name "/8_1438937158") (class "Default")
      (node (ref "JP11") (pin "9") (pinfunction "9_9") (pintype "passive"))
      (node (ref "JP126") (pin "4") (pinfunction "4_4") (pintype "passive"))
    )
    (net (code "260") (name "/8_1438937250") (class "Default")
      (node (ref "JP137") (pin "4") (pinfunction "4_4") (pintype "passive"))
      (node (ref "JP9") (pin "7") (pinfunction "7_7") (pintype "passive"))
    )
    (net (code "261") (name "/8_1438937291") (class "Default")
      (node (ref "JP60") (pin "4") (pinfunction "4_4") (pintype "passive"))
      (node (ref "JP7") (pin "9") (pinfunction "9_9") (pintype "passive"))
    )
    (net (code "262") (name "/8_1438937340") (class "Default")
      (node (ref "JP5") (pin "14") (pinfunction "14_14") (pintype "passive"))
      (node (ref "JP65") (pin "4") (pinfunction "4_4") (pintype "passive"))
    )
    (net (code "263") (name "/8_1438937363") (class "Default")
      (node (ref "JP3") (pin "9") (pinfunction "9_9") (pintype "passive"))
      (node (ref "JP48") (pin "4") (pinfunction "4_4") (pintype "passive"))
    )
    (net (code "264") (name "/8_1438937434") (class "Default")
      (node (ref "JP1") (pin "14") (pinfunction "14_14") (pintype "passive"))
      (node (ref "JP53") (pin "4") (pinfunction "4_4") (pintype "passive"))
    )
    (net (code "265") (name "/9_1438935726") (class "Default")
      (node (ref "JP133") (pin "5") (pinfunction "5_5") (pintype "passive"))
      (node (ref "JP21") (pin "10") (pinfunction "10_10") (pintype "passive"))
    )
    (net (code "266") (name "/9_1438935777") (class "Default")
      (node (ref "JP109") (pin "5") (pinfunction "5_5") (pintype "passive"))
      (node (ref "JP23") (pin "10") (pinfunction "10_10") (pintype "passive"))
    )
    (net (code "267") (name "/9_1438935968") (class "Default")
      (node (ref "JP161") (pin "5") (pinfunction "5_5") (pintype "passive"))
      (node (ref "JP25") (pin "6") (pinfunction "6_6") (pintype "passive"))
    )
    (net (code "268") (name "/9_1438936077") (class "Default")
      (node (ref "JP27") (pin "6") (pinfunction "6_6") (pintype "passive"))
      (node (ref "JP79") (pin "5") (pinfunction "5_5") (pintype "passive"))
    )
    (net (code "269") (name "/9_1438936131") (class "Default")
      (node (ref "JP29") (pin "10") (pinfunction "10_10") (pintype "passive"))
      (node (ref "JP91") (pin "5") (pinfunction "5_5") (pintype "passive"))
    )
    (net (code "270") (name "/9_1438936228") (class "Default")
      (node (ref "JP114") (pin "5") (pinfunction "5_5") (pintype "passive"))
      (node (ref "JP31") (pin "10") (pinfunction "10_10") (pintype "passive"))
    )
    (net (code "271") (name "/9_1438936418") (class "Default")
      (node (ref "JP107") (pin "5") (pinfunction "5_5") (pintype "passive"))
      (node (ref "JP33") (pin "6") (pinfunction "6_6") (pintype "passive"))
    )
    (net (code "272") (name "/9_1438936529") (class "Default")
      (node (ref "JP35") (pin "6") (pinfunction "6_6") (pintype "passive"))
      (node (ref "JP78") (pin "5") (pinfunction "5_5") (pintype "passive"))
    )
    (net (code "273") (name "/9_1438936852") (class "Default")
      (node (ref "JP37") (pin "10") (pinfunction "10_10") (pintype "passive"))
      (node (ref "JP84") (pin "5") (pinfunction "5_5") (pintype "passive"))
    )
    (net (code "274") (name "/9_1438936896") (class "Default")
      (node (ref "JP39") (pin "15") (pinfunction "15_15") (pintype "passive"))
      (node (ref "JP95") (pin "5") (pinfunction "5_5") (pintype "passive"))
    )
    (net (code "275") (name "/9_1438936925") (class "Default")
      (node (ref "JP131") (pin "5") (pinfunction "5_5") (pintype "passive"))
      (node (ref "JP19") (pin "10") (pinfunction "10_10") (pintype "passive"))
    )
    (net (code "276") (name "/9_1438936986") (class "Default")
      (node (ref "JP157") (pin "5") (pinfunction "5_5") (pintype "passive"))
      (node (ref "JP17") (pin "6") (pinfunction "6_6") (pintype "passive"))
    )
    (net (code "277") (name "/9_1438937040") (class "Default")
      (node (ref "JP119") (pin "5") (pinfunction "5_5") (pintype "passive"))
      (node (ref "JP15") (pin "10") (pinfunction "10_10") (pintype "passive"))
    )
    (net (code "278") (name "/9_1438937110") (class "Default")
      (node (ref "JP13") (pin "5") (pinfunction "5_5") (pintype "passive"))
      (node (ref "JP155") (pin "5") (pinfunction "5_5") (pintype "passive"))
    )
    (net (code "279") (name "/9_1438937158") (class "Default")
      (node (ref "JP11") (pin "10") (pinfunction "10_10") (pintype "passive"))
      (node (ref "JP126") (pin "5") (pinfunction "5_5") (pintype "passive"))
    )
    (net (code "280") (name "/9_1438937250") (class "Default")
      (node (ref "JP137") (pin "5") (pinfunction "5_5") (pintype "passive"))
      (node (ref "JP9") (pin "6") (pinfunction "6_6") (pintype "passive"))
    )
    (net (code "281") (name "/9_1438937291") (class "Default")
      (node (ref "JP60") (pin "5") (pinfunction "5_5") (pintype "passive"))
      (node (ref "JP7") (pin "10") (pinfunction "10_10") (pintype "passive"))
    )
    (net (code "282") (name "/9_1438937340") (class "Default")
      (node (ref "JP5") (pin "15") (pinfunction "15_15") (pintype "passive"))
      (node (ref "JP65") (pin "5") (pinfunction "5_5") (pintype "passive"))
    )
    (net (code "283") (name "/9_1438937363") (class "Default")
      (node (ref "JP3") (pin "10") (pinfunction "10_10") (pintype "passive"))
      (node (ref "JP48") (pin "5") (pinfunction "5_5") (pintype "passive"))
    )
    (net (code "284") (name "/9_1438937434") (class "Default")
      (node (ref "JP1") (pin "15") (pinfunction "15_15") (pintype "passive"))
      (node (ref "JP53") (pin "5") (pinfunction "5_5") (pintype "passive"))
    )
    (net (code "285") (name "/10_1438936896") (class "Default")
      (node (ref "JP39") (pin "5") (pinfunction "5_5") (pintype "passive"))
      (node (ref "JP96") (pin "1") (pinfunction "1_1") (pintype "passive"))
    )
    (net (code "286") (name "/10_1438937340") (class "Default")
      (node (ref "JP5") (pin "5") (pinfunction "5_5") (pintype "passive"))
      (node (ref "JP66") (pin "1") (pinfunction "1_1") (pintype "passive"))
    )
    (net (code "287") (name "/10_1438937434") (class "Default")
      (node (ref "JP1") (pin "5") (pinfunction "5_5") (pintype "passive"))
      (node (ref "JP54") (pin "1") (pinfunction "1_1") (pintype "passive"))
    )
    (net (code "288") (name "/11_1438936896") (class "Default")
      (node (ref "JP39") (pin "4") (pinfunction "4_4") (pintype "passive"))
      (node (ref "JP96") (pin "2") (pinfunction "2_2") (pintype "passive"))
    )
    (net (code "289") (name "/11_1438937340") (class "Default")
      (node (ref "JP5") (pin "4") (pinfunction "4_4") (pintype "passive"))
      (node (ref "JP66") (pin "2") (pinfunction "2_2") (pintype "passive"))
    )
    (net (code "290") (name "/11_1438937434") (class "Default")
      (node (ref "JP1") (pin "4") (pinfunction "4_4") (pintype "passive"))
      (node (ref "JP54") (pin "2") (pinfunction "2_2") (pintype "passive"))
    )
    (net (code "291") (name "/12_1438936896") (class "Default")
      (node (ref "JP39") (pin "3") (pinfunction "3_3") (pintype "passive"))
      (node (ref "JP96") (pin "3") (pinfunction "3_3") (pintype "passive"))
    )
    (net (code "292") (name "/12_1438937340") (class "Default")
      (node (ref "JP5") (pin "3") (pinfunction "3_3") (pintype "passive"))
      (node (ref "JP66") (pin "3") (pinfunction "3_3") (pintype "passive"))
    )
    (net (code "293") (name "/12_1438937434") (class "Default")
      (node (ref "JP1") (pin "3") (pinfunction "3_3") (pintype "passive"))
      (node (ref "JP54") (pin "3") (pinfunction "3_3") (pintype "passive"))
    )
    (net (code "294") (name "/13_1438936896") (class "Default")
      (node (ref "JP39") (pin "2") (pinfunction "2_2") (pintype "passive"))
      (node (ref "JP96") (pin "4") (pinfunction "4_4") (pintype "passive"))
    )
    (net (code "295") (name "/13_1438937340") (class "Default")
      (node (ref "JP5") (pin "2") (pinfunction "2_2") (pintype "passive"))
      (node (ref "JP66") (pin "4") (pinfunction "4_4") (pintype "passive"))
    )
    (net (code "296") (name "/13_1438937434") (class "Default")
      (node (ref "JP1") (pin "2") (pinfunction "2_2") (pintype "passive"))
      (node (ref "JP54") (pin "4") (pinfunction "4_4") (pintype "passive"))
    )
    (net (code "297") (name "/14_1438936896") (class "Default")
      (node (ref "JP39") (pin "1") (pinfunction "1_1") (pintype "passive"))
      (node (ref "JP96") (pin "5") (pinfunction "5_5") (pintype "passive"))
    )
    (net (code "298") (name "/14_1438937340") (class "Default")
      (node (ref "JP5") (pin "1") (pinfunction "1_1") (pintype "passive"))
      (node (ref "JP66") (pin "5") (pinfunction "5_5") (pintype "passive"))
    )
    (net (code "299") (name "/14_1438937434") (class "Default")
      (node (ref "JP1") (pin "1") (pinfunction "1_1") (pintype "passive"))
      (node (ref "JP54") (pin "5") (pinfunction "5_5") (pintype "passive"))
    )
    (net (code "300") (name "/CLEAN25") (class "Default")
      (node (ref "JP3") (pin "11") (pinfunction "11_11") (pintype "passive"))
    )
    (net (code "301") (name "/CLEAN104") (class "Default")
      (node (ref "JP13") (pin "15") (pinfunction "15_15") (pintype "passive"))
    )
    (net (code "302") (name "/CLEAN255") (class "Default")
      (node (ref "JP35") (pin "1") (pinfunction "1_1") (pintype "passive"))
    )
    (net (code "303") (name "/CLEAN519") (class "Default")
      (node (ref "JP127") (pin "5") (pinfunction "5_5") (pintype "passive"))
    )
  )
)
